# ES_Daisy_Patch_Rev4.net
KiCad netlist of a schematic drawn in EAGLE
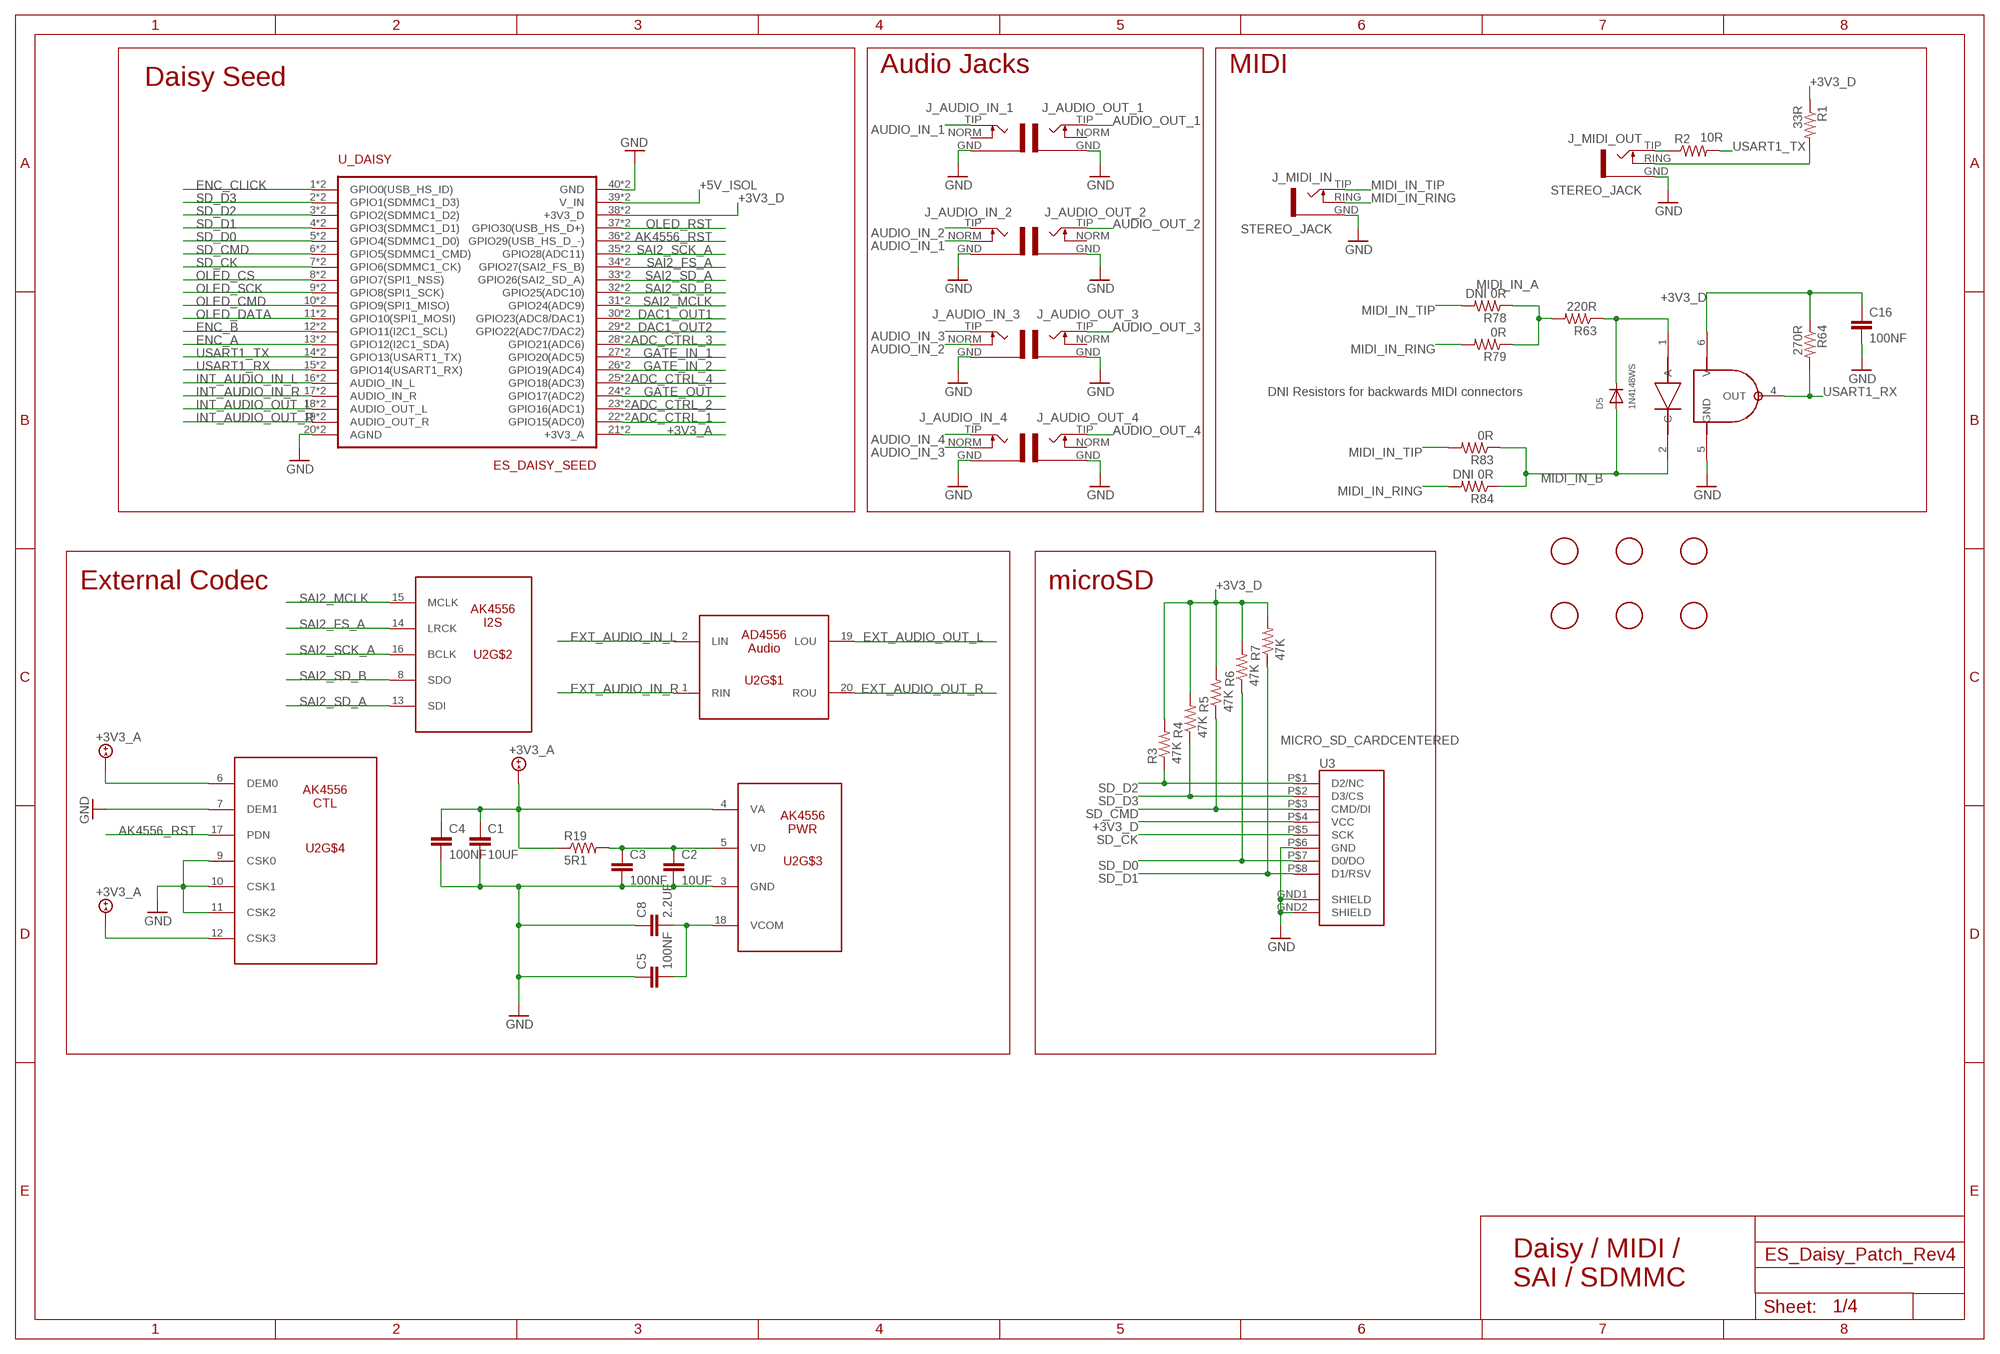
[diagram p0: schematic, sheet 1]
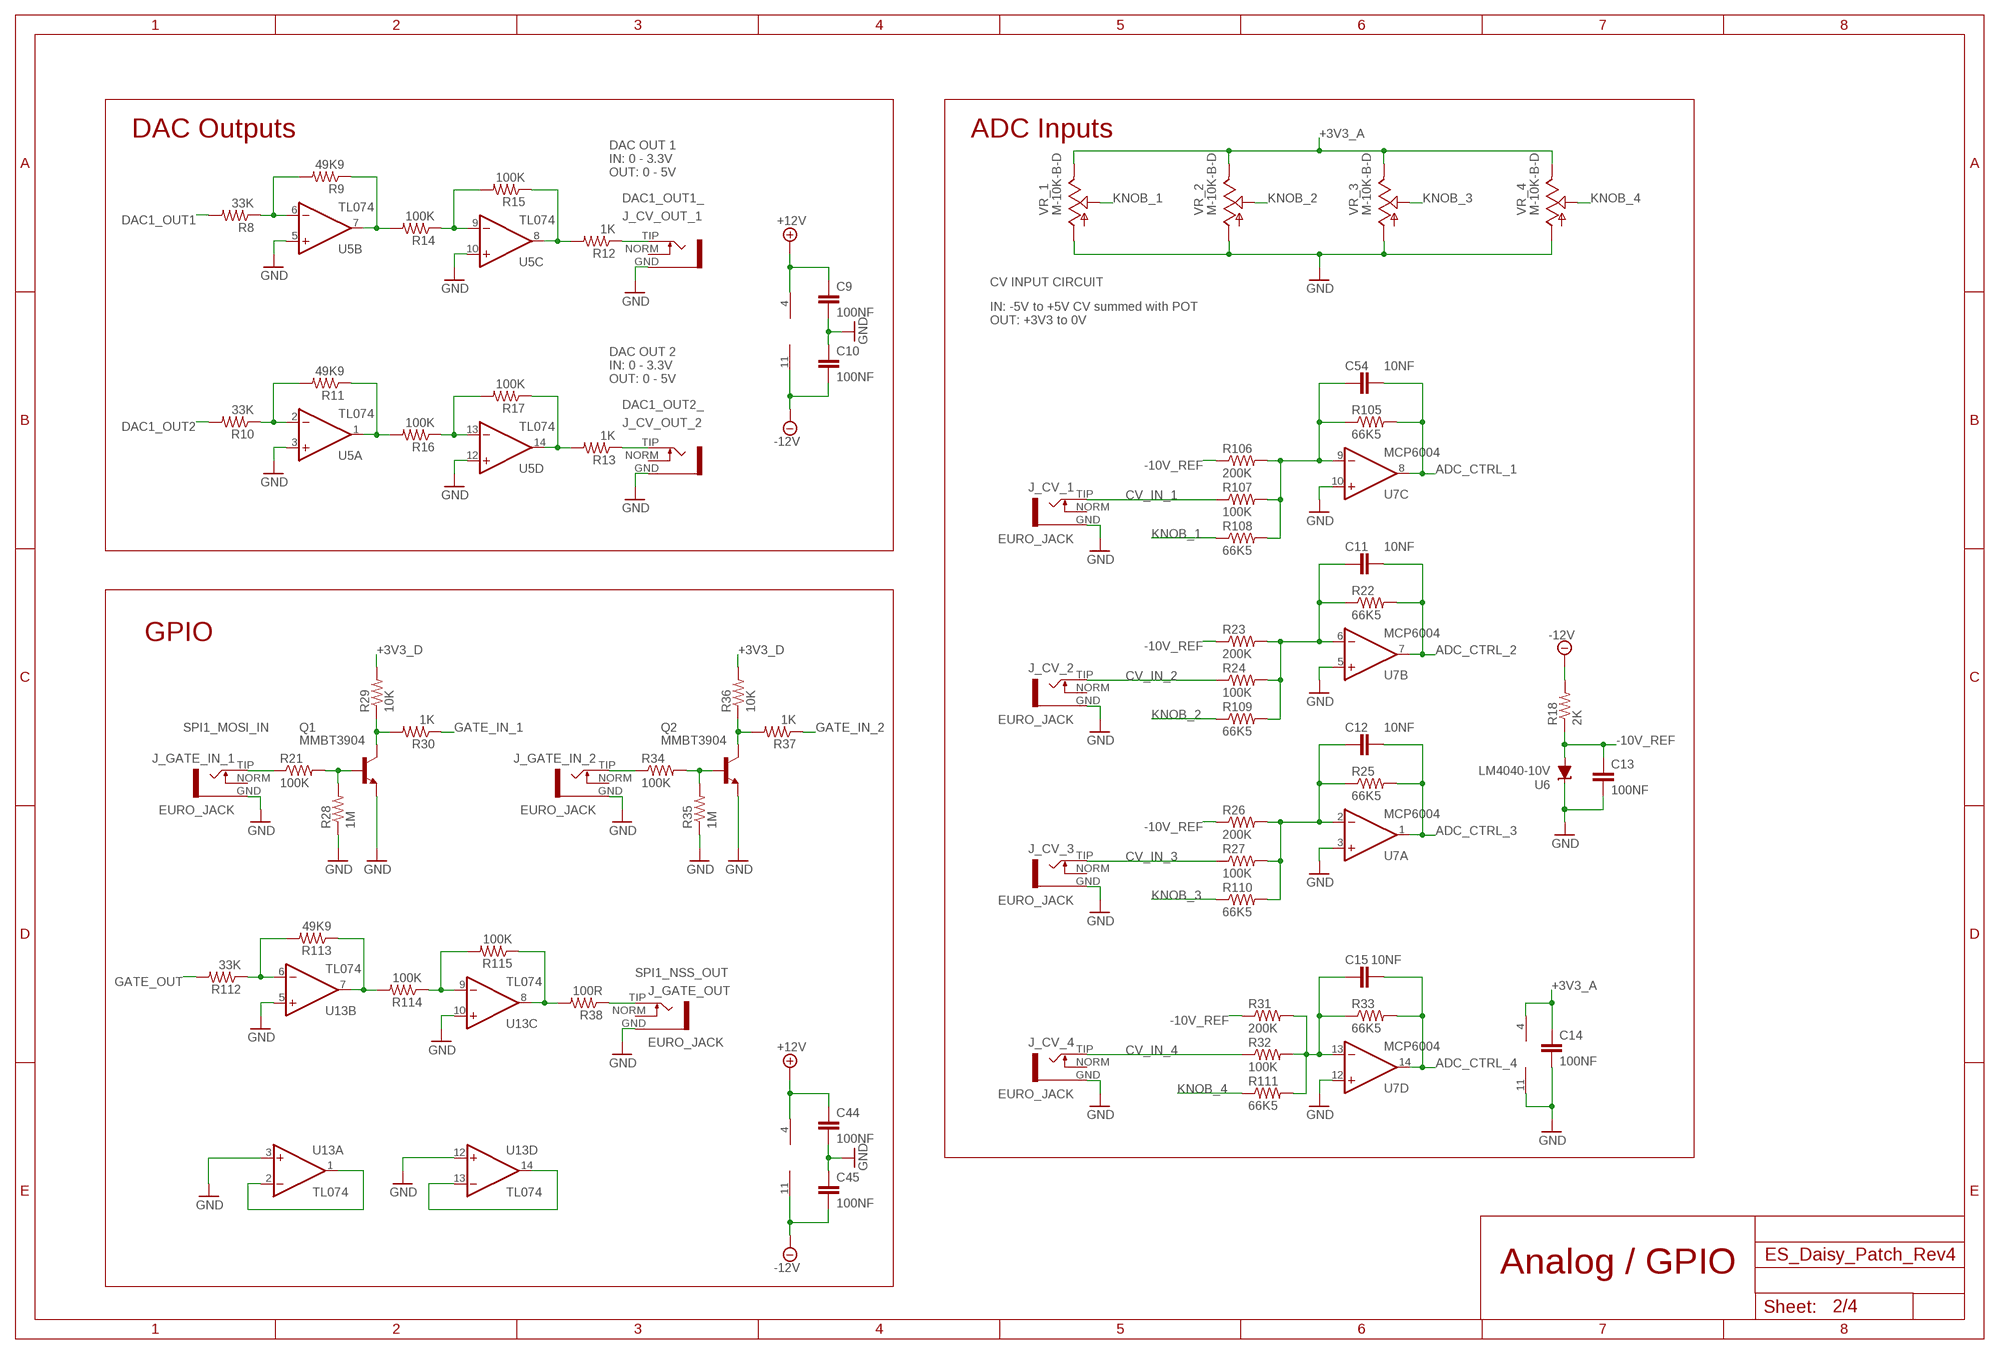
[diagram p1: schematic, sheet 2]
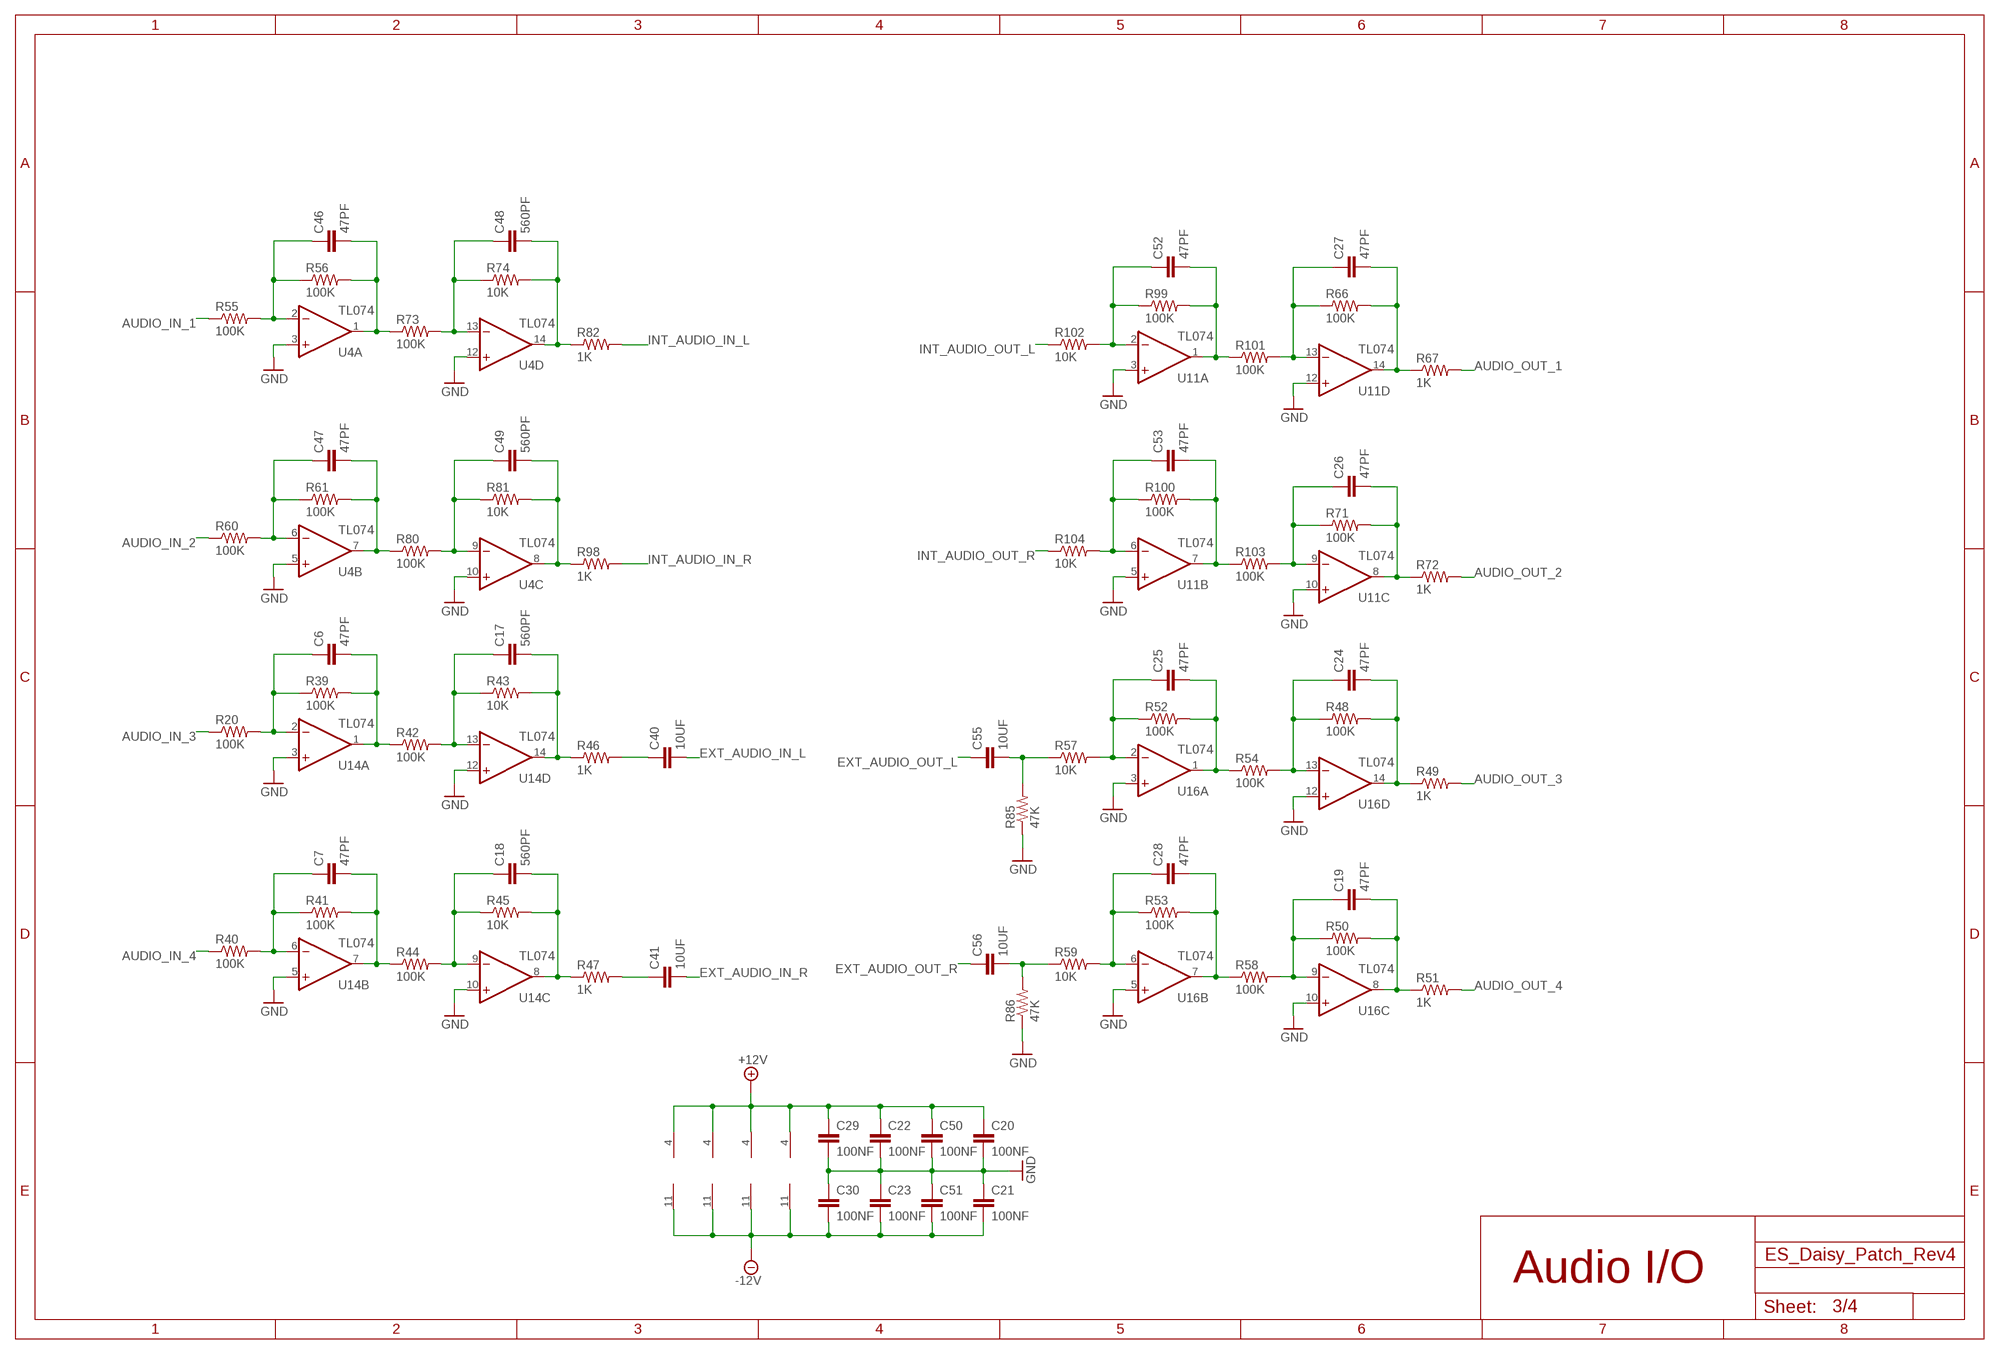
[diagram p2: schematic, sheet 3]
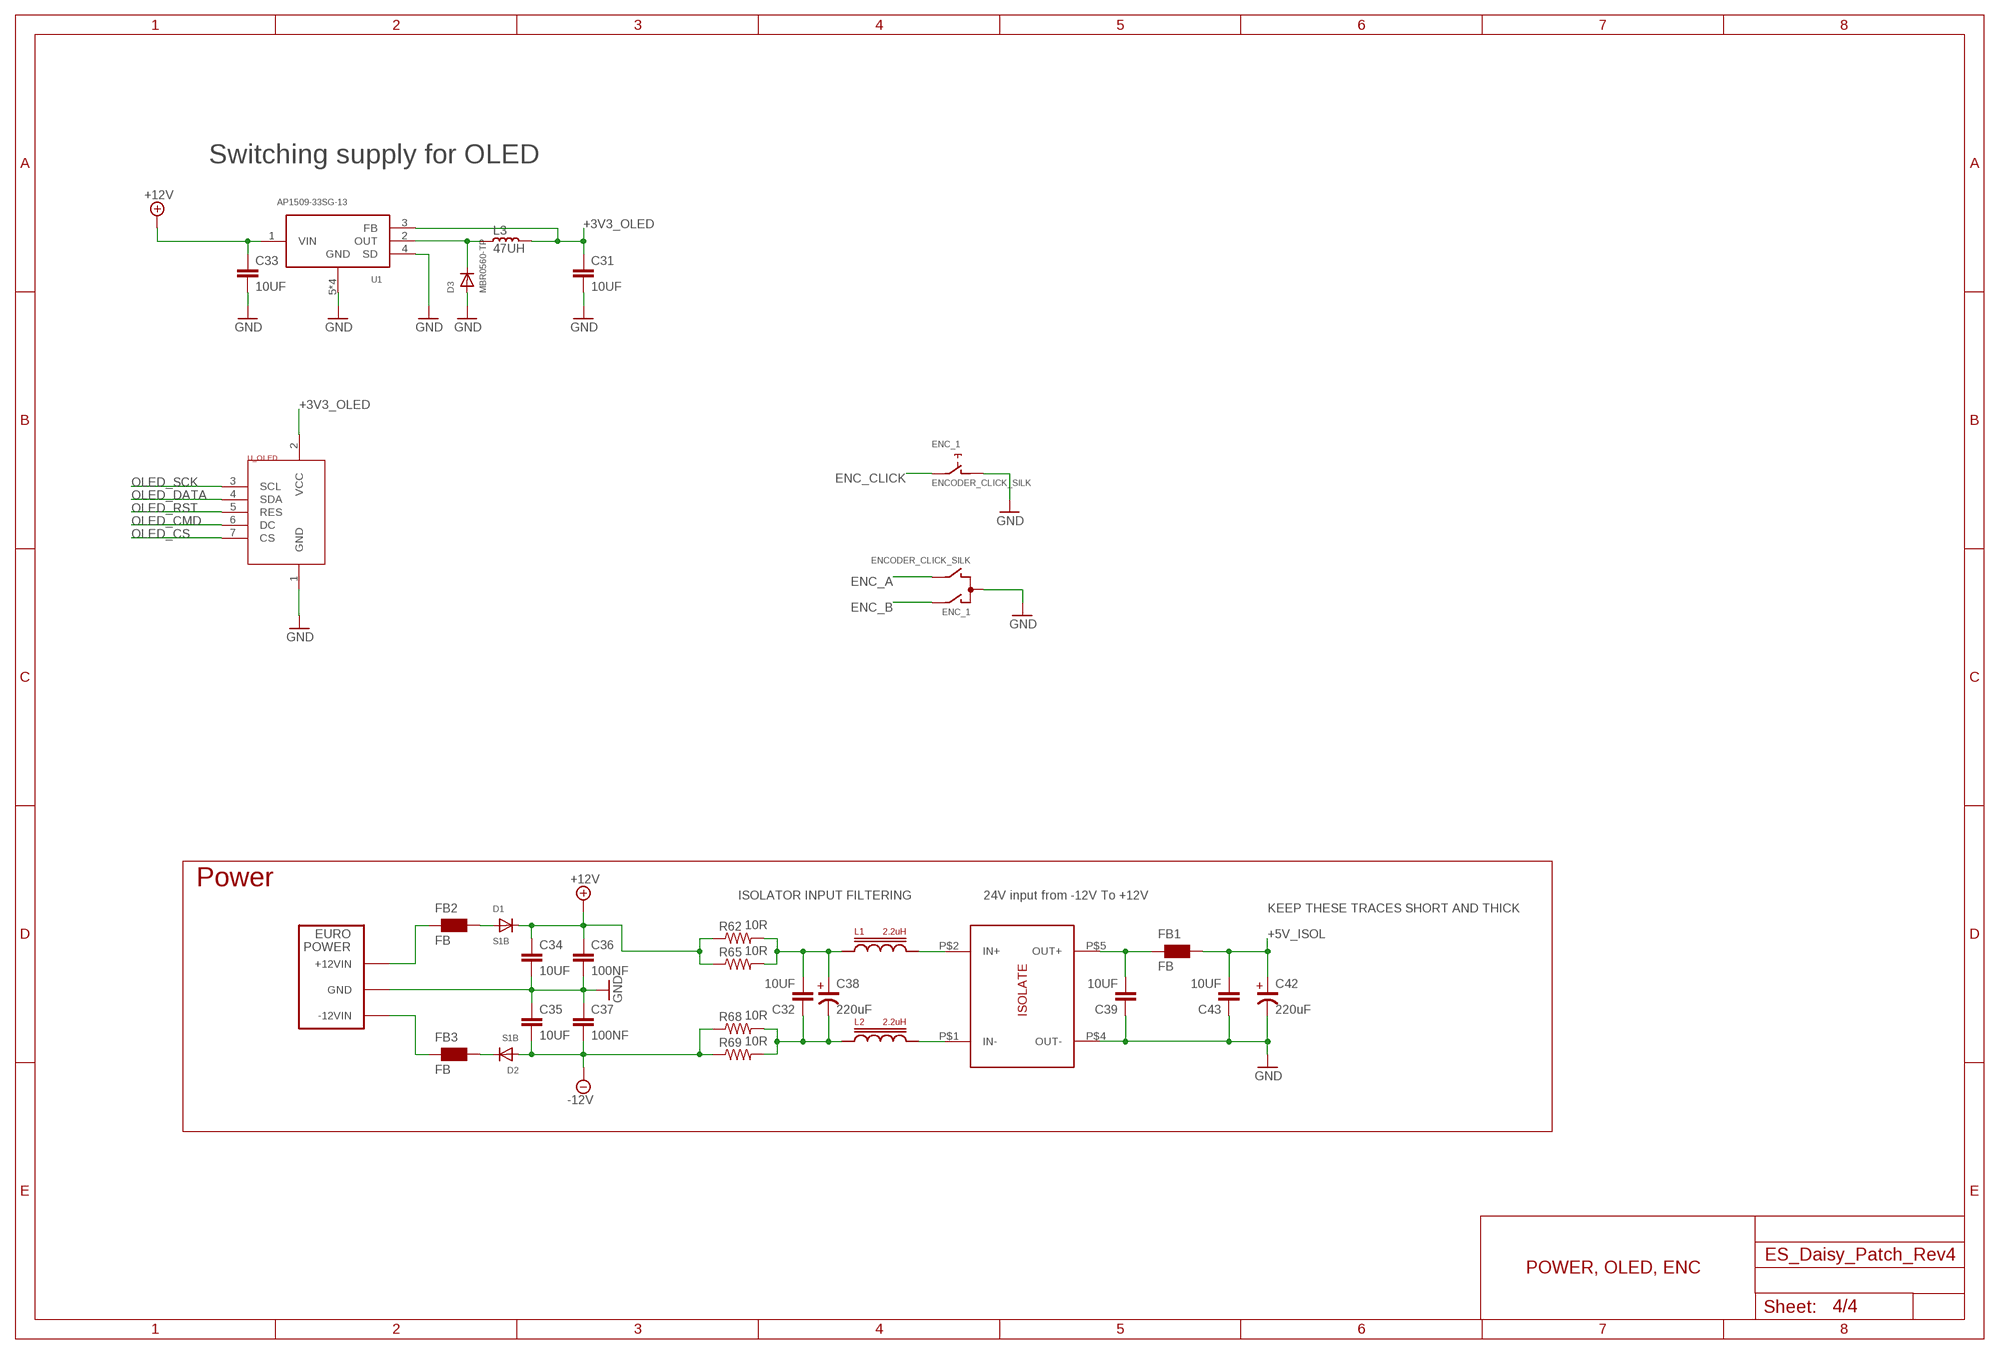
[diagram p3: schematic, sheet 4]

(export (version "E")
  (design (tool "Eeschema 10.0.6"))
  (components
    (comp (ref "C6")
      (value "47PF")
      (footprint "eagle-import:C0603")
      (libsource (lib "eagle-import") (part "Electrosmith-Passives_C-EUC0603"))
    )
    (comp (ref "C7")
      (value "47PF")
      (footprint "eagle-import:C0603")
      (libsource (lib "eagle-import") (part "Electrosmith-Passives_C-EUC0603"))
    )
    (comp (ref "C17")
      (value "560PF")
      (footprint "eagle-import:C0603")
      (libsource (lib "eagle-import") (part "Electrosmith-Passives_C-EUC0603"))
    )
    (comp (ref "C18")
      (value "560PF")
      (footprint "eagle-import:C0603")
      (libsource (lib "eagle-import") (part "Electrosmith-Passives_C-EUC0603"))
    )
    (comp (ref "C19")
      (value "47PF")
      (footprint "eagle-import:C0603")
      (libsource (lib "eagle-import") (part "Electrosmith-Passives_C-EUC0603"))
    )
    (comp (ref "C20")
      (value "100NF")
      (footprint "eagle-import:C0603")
      (libsource (lib "eagle-import") (part "Electrosmith-Passives_C-EUC0603"))
    )
    (comp (ref "C21")
      (value "100NF")
      (footprint "eagle-import:C0603")
      (libsource (lib "eagle-import") (part "Electrosmith-Passives_C-EUC0603"))
    )
    (comp (ref "C22")
      (value "100NF")
      (footprint "eagle-import:C0603")
      (libsource (lib "eagle-import") (part "Electrosmith-Passives_C-EUC0603"))
    )
    (comp (ref "C23")
      (value "100NF")
      (footprint "eagle-import:C0603")
      (libsource (lib "eagle-import") (part "Electrosmith-Passives_C-EUC0603"))
    )
    (comp (ref "C24")
      (value "47PF")
      (footprint "eagle-import:C0603")
      (libsource (lib "eagle-import") (part "Electrosmith-Passives_C-EUC0603"))
    )
    (comp (ref "C25")
      (value "47PF")
      (footprint "eagle-import:C0603")
      (libsource (lib "eagle-import") (part "Electrosmith-Passives_C-EUC0603"))
    )
    (comp (ref "C26")
      (value "47PF")
      (footprint "eagle-import:C0603")
      (libsource (lib "eagle-import") (part "Electrosmith-Passives_C-EUC0603"))
    )
    (comp (ref "C27")
      (value "47PF")
      (footprint "eagle-import:C0603")
      (libsource (lib "eagle-import") (part "Electrosmith-Passives_C-EUC0603"))
    )
    (comp (ref "C28")
      (value "47PF")
      (footprint "eagle-import:C0603")
      (libsource (lib "eagle-import") (part "Electrosmith-Passives_C-EUC0603"))
    )
    (comp (ref "C29")
      (value "100NF")
      (footprint "eagle-import:C0603")
      (libsource (lib "eagle-import") (part "Electrosmith-Passives_C-EUC0603"))
    )
    (comp (ref "C30")
      (value "100NF")
      (footprint "eagle-import:C0603")
      (libsource (lib "eagle-import") (part "Electrosmith-Passives_C-EUC0603"))
    )
    (comp (ref "C40")
      (value "10UF")
      (footprint "eagle-import:C0805")
      (libsource (lib "eagle-import") (part "Electrosmith-Passives_C-EUC0805"))
    )
    (comp (ref "C41")
      (value "10UF")
      (footprint "eagle-import:C0805")
      (libsource (lib "eagle-import") (part "Electrosmith-Passives_C-EUC0805"))
    )
    (comp (ref "C46")
      (value "47PF")
      (footprint "eagle-import:C0603")
      (libsource (lib "eagle-import") (part "Electrosmith-Passives_C-EUC0603"))
    )
    (comp (ref "C47")
      (value "47PF")
      (footprint "eagle-import:C0603")
      (libsource (lib "eagle-import") (part "Electrosmith-Passives_C-EUC0603"))
    )
    (comp (ref "C48")
      (value "560PF")
      (footprint "eagle-import:C0603")
      (libsource (lib "eagle-import") (part "Electrosmith-Passives_C-EUC0603"))
    )
    (comp (ref "C49")
      (value "560PF")
      (footprint "eagle-import:C0603")
      (libsource (lib "eagle-import") (part "Electrosmith-Passives_C-EUC0603"))
    )
    (comp (ref "C50")
      (value "100NF")
      (footprint "eagle-import:C0603")
      (libsource (lib "eagle-import") (part "Electrosmith-Passives_C-EUC0603"))
    )
    (comp (ref "C51")
      (value "100NF")
      (footprint "eagle-import:C0603")
      (libsource (lib "eagle-import") (part "Electrosmith-Passives_C-EUC0603"))
    )
    (comp (ref "C52")
      (value "47PF")
      (footprint "eagle-import:C0603")
      (libsource (lib "eagle-import") (part "Electrosmith-Passives_C-EUC0603"))
    )
    (comp (ref "C53")
      (value "47PF")
      (footprint "eagle-import:C0603")
      (libsource (lib "eagle-import") (part "Electrosmith-Passives_C-EUC0603"))
    )
    (comp (ref "C55")
      (value "10UF")
      (footprint "eagle-import:C0805")
      (libsource (lib "eagle-import") (part "Electrosmith-Passives_C-EUC0805"))
    )
    (comp (ref "C56")
      (value "10UF")
      (footprint "eagle-import:C0805")
      (libsource (lib "eagle-import") (part "Electrosmith-Passives_C-EUC0805"))
    )
    (comp (ref "R20")
      (value "100K")
      (footprint "eagle-import:R0603")
      (libsource (lib "eagle-import") (part "R-US_R0603"))
    )
    (comp (ref "R39")
      (value "100K")
      (footprint "eagle-import:R0603")
      (libsource (lib "eagle-import") (part "R-US_R0603"))
    )
    (comp (ref "R40")
      (value "100K")
      (footprint "eagle-import:R0603")
      (libsource (lib "eagle-import") (part "R-US_R0603"))
    )
    (comp (ref "R41")
      (value "100K")
      (footprint "eagle-import:R0603")
      (libsource (lib "eagle-import") (part "R-US_R0603"))
    )
    (comp (ref "R42")
      (value "100K")
      (footprint "eagle-import:R0603")
      (libsource (lib "eagle-import") (part "R-US_R0603"))
    )
    (comp (ref "R43")
      (value "10K")
      (footprint "eagle-import:R0603")
      (libsource (lib "eagle-import") (part "R-US_R0603"))
    )
    (comp (ref "R44")
      (value "100K")
      (footprint "eagle-import:R0603")
      (libsource (lib "eagle-import") (part "R-US_R0603"))
    )
    (comp (ref "R45")
      (value "10K")
      (footprint "eagle-import:R0603")
      (libsource (lib "eagle-import") (part "R-US_R0603"))
    )
    (comp (ref "R46")
      (value "1K")
      (footprint "eagle-import:R0603")
      (libsource (lib "eagle-import") (part "R-US_R0603"))
    )
    (comp (ref "R47")
      (value "1K")
      (footprint "eagle-import:R0603")
      (libsource (lib "eagle-import") (part "R-US_R0603"))
    )
    (comp (ref "R48")
      (value "100K")
      (footprint "eagle-import:R0603")
      (libsource (lib "eagle-import") (part "R-US_R0603"))
    )
    (comp (ref "R49")
      (value "1K")
      (footprint "eagle-import:R0603")
      (libsource (lib "eagle-import") (part "R-US_R0603"))
    )
    (comp (ref "R50")
      (value "100K")
      (footprint "eagle-import:R0603")
      (libsource (lib "eagle-import") (part "R-US_R0603"))
    )
    (comp (ref "R51")
      (value "1K")
      (footprint "eagle-import:R0603")
      (libsource (lib "eagle-import") (part "R-US_R0603"))
    )
    (comp (ref "R52")
      (value "100K")
      (footprint "eagle-import:R0603")
      (libsource (lib "eagle-import") (part "R-US_R0603"))
    )
    (comp (ref "R53")
      (value "100K")
      (footprint "eagle-import:R0603")
      (libsource (lib "eagle-import") (part "R-US_R0603"))
    )
    (comp (ref "R54")
      (value "100K")
      (footprint "eagle-import:R0603")
      (libsource (lib "eagle-import") (part "R-US_R0603"))
    )
    (comp (ref "R55")
      (value "100K")
      (footprint "eagle-import:R0603")
      (libsource (lib "eagle-import") (part "R-US_R0603"))
    )
    (comp (ref "R56")
      (value "100K")
      (footprint "eagle-import:R0603")
      (libsource (lib "eagle-import") (part "R-US_R0603"))
    )
    (comp (ref "R57")
      (value "10K")
      (footprint "eagle-import:R0603")
      (libsource (lib "eagle-import") (part "R-US_R0603"))
    )
    (comp (ref "R58")
      (value "100K")
      (footprint "eagle-import:R0603")
      (libsource (lib "eagle-import") (part "R-US_R0603"))
    )
    (comp (ref "R59")
      (value "10K")
      (footprint "eagle-import:R0603")
      (libsource (lib "eagle-import") (part "R-US_R0603"))
    )
    (comp (ref "R60")
      (value "100K")
      (footprint "eagle-import:R0603")
      (libsource (lib "eagle-import") (part "R-US_R0603"))
    )
    (comp (ref "R61")
      (value "100K")
      (footprint "eagle-import:R0603")
      (libsource (lib "eagle-import") (part "R-US_R0603"))
    )
    (comp (ref "R66")
      (value "100K")
      (footprint "eagle-import:R0603")
      (libsource (lib "eagle-import") (part "R-US_R0603"))
    )
    (comp (ref "R67")
      (value "1K")
      (footprint "eagle-import:R0603")
      (libsource (lib "eagle-import") (part "R-US_R0603"))
    )
    (comp (ref "R71")
      (value "100K")
      (footprint "eagle-import:R0603")
      (libsource (lib "eagle-import") (part "R-US_R0603"))
    )
    (comp (ref "R72")
      (value "1K")
      (footprint "eagle-import:R0603")
      (libsource (lib "eagle-import") (part "R-US_R0603"))
    )
    (comp (ref "R73")
      (value "100K")
      (footprint "eagle-import:R0603")
      (libsource (lib "eagle-import") (part "R-US_R0603"))
    )
    (comp (ref "R74")
      (value "10K")
      (footprint "eagle-import:R0603")
      (libsource (lib "eagle-import") (part "R-US_R0603"))
    )
    (comp (ref "R80")
      (value "100K")
      (footprint "eagle-import:R0603")
      (libsource (lib "eagle-import") (part "R-US_R0603"))
    )
    (comp (ref "R81")
      (value "10K")
      (footprint "eagle-import:R0603")
      (libsource (lib "eagle-import") (part "R-US_R0603"))
    )
    (comp (ref "R82")
      (value "1K")
      (footprint "eagle-import:R0603")
      (libsource (lib "eagle-import") (part "R-US_R0603"))
    )
    (comp (ref "R85")
      (value "47K")
      (footprint "eagle-import:R0603")
      (libsource (lib "eagle-import") (part "R-US_R0603"))
    )
    (comp (ref "R86")
      (value "47K")
      (footprint "eagle-import:R0603")
      (libsource (lib "eagle-import") (part "R-US_R0603"))
    )
    (comp (ref "R98")
      (value "1K")
      (footprint "eagle-import:R0603")
      (libsource (lib "eagle-import") (part "R-US_R0603"))
    )
    (comp (ref "R99")
      (value "100K")
      (footprint "eagle-import:R0603")
      (libsource (lib "eagle-import") (part "R-US_R0603"))
    )
    (comp (ref "R100")
      (value "100K")
      (footprint "eagle-import:R0603")
      (libsource (lib "eagle-import") (part "R-US_R0603"))
    )
    (comp (ref "R101")
      (value "100K")
      (footprint "eagle-import:R0603")
      (libsource (lib "eagle-import") (part "R-US_R0603"))
    )
    (comp (ref "R102")
      (value "10K")
      (footprint "eagle-import:R0603")
      (libsource (lib "eagle-import") (part "R-US_R0603"))
    )
    (comp (ref "R103")
      (value "100K")
      (footprint "eagle-import:R0603")
      (libsource (lib "eagle-import") (part "R-US_R0603"))
    )
    (comp (ref "R104")
      (value "10K")
      (footprint "eagle-import:R0603")
      (libsource (lib "eagle-import") (part "R-US_R0603"))
    )
    (comp (ref "U4")
      (value "TL074")
      (footprint "eagle-import:TSSOP-14")
      (fields (field (name "MPN") "TL074CPWR"))
      (libsource (lib "eagle-import") (part "TL074_TSSOP-14"))
    )
    (comp (ref "U11")
      (value "TL074")
      (footprint "eagle-import:TSSOP-14")
      (fields (field (name "MPN") "TL074CPWR"))
      (libsource (lib "eagle-import") (part "TL074_TSSOP-14"))
    )
    (comp (ref "U14")
      (value "TL074")
      (footprint "eagle-import:TSSOP-14")
      (fields (field (name "MPN") "TL074CPWR"))
      (libsource (lib "eagle-import") (part "TL074_TSSOP-14"))
    )
    (comp (ref "U16")
      (value "TL074")
      (footprint "eagle-import:TSSOP-14")
      (fields (field (name "MPN") "TL074CPWR"))
      (libsource (lib "eagle-import") (part "TL074_TSSOP-14"))
    )
    (comp (ref "C1")
      (value "10UF")
      (footprint "eagle-import:C0805")
      (libsource (lib "eagle-import") (part "Electrosmith-Passives_C-EUC0805"))
    )
    (comp (ref "C2")
      (value "10UF")
      (footprint "eagle-import:C0805")
      (libsource (lib "eagle-import") (part "Electrosmith-Passives_C-EUC0805"))
    )
    (comp (ref "C3")
      (value "100NF")
      (footprint "eagle-import:C0603")
      (libsource (lib "eagle-import") (part "Electrosmith-Passives_C-EUC0603"))
    )
    (comp (ref "C4")
      (value "100NF")
      (footprint "eagle-import:C0603")
      (libsource (lib "eagle-import") (part "Electrosmith-Passives_C-EUC0603"))
    )
    (comp (ref "C5")
      (value "100NF")
      (footprint "eagle-import:C0603")
      (libsource (lib "eagle-import") (part "Electrosmith-Passives_C-EUC0603"))
    )
    (comp (ref "C8")
      (value "2.2UF")
      (footprint "eagle-import:C0603")
      (libsource (lib "eagle-import") (part "Electrosmith-Passives_C-EUC0603"))
    )
    (comp (ref "C16")
      (value "100NF")
      (footprint "eagle-import:C0603")
      (libsource (lib "eagle-import") (part "Electrosmith-Passives_C-EUC0603"))
    )
    (comp (ref "D5")
      (value "1N4148WS")
      (footprint "eagle-import:SOD-323F")
      (libsource (lib "eagle-import") (part "DIODE_SOD-323F"))
    )
    (comp (ref "FD1")
      (value "FIDUCIAL")
      (footprint "eagle-import:FIDUCIAL_1MM")
      (libsource (lib "eagle-import") (part "FIDUCIAL"))
    )
    (comp (ref "FD2")
      (value "FIDUCIAL")
      (footprint "eagle-import:FIDUCIAL_1MM")
      (libsource (lib "eagle-import") (part "FIDUCIAL"))
    )
    (comp (ref "FD3")
      (value "FIDUCIAL")
      (footprint "eagle-import:FIDUCIAL_1MM")
      (libsource (lib "eagle-import") (part "FIDUCIAL"))
    )
    (comp (ref "FD4")
      (value "FIDUCIAL")
      (footprint "eagle-import:FIDUCIAL_1MM")
      (libsource (lib "eagle-import") (part "FIDUCIAL"))
    )
    (comp (ref "FD5")
      (value "FIDUCIAL")
      (footprint "eagle-import:FIDUCIAL_1MM")
      (libsource (lib "eagle-import") (part "FIDUCIAL"))
    )
    (comp (ref "FD6")
      (value "FIDUCIAL")
      (footprint "eagle-import:FIDUCIAL_1MM")
      (libsource (lib "eagle-import") (part "FIDUCIAL"))
    )
    (comp (ref "J_AUDIO_IN_1")
      (value "EURO_JACK")
      (footprint "eagle-import:S_JACK")
      (libsource (lib "eagle-import") (part "EURO_JACK"))
    )
    (comp (ref "J_AUDIO_IN_2")
      (value "EURO_JACK")
      (footprint "eagle-import:S_JACK")
      (libsource (lib "eagle-import") (part "EURO_JACK"))
    )
    (comp (ref "J_AUDIO_IN_3")
      (value "EURO_JACK")
      (footprint "eagle-import:S_JACK")
      (libsource (lib "eagle-import") (part "EURO_JACK"))
    )
    (comp (ref "J_AUDIO_IN_4")
      (value "EURO_JACK")
      (footprint "eagle-import:S_JACK")
      (libsource (lib "eagle-import") (part "EURO_JACK"))
    )
    (comp (ref "J_AUDIO_OUT_1")
      (value "EURO_JACK")
      (footprint "eagle-import:S_JACK")
      (libsource (lib "eagle-import") (part "EURO_JACK"))
    )
    (comp (ref "J_AUDIO_OUT_2")
      (value "EURO_JACK")
      (footprint "eagle-import:S_JACK")
      (libsource (lib "eagle-import") (part "EURO_JACK"))
    )
    (comp (ref "J_AUDIO_OUT_3")
      (value "EURO_JACK")
      (footprint "eagle-import:S_JACK")
      (libsource (lib "eagle-import") (part "EURO_JACK"))
    )
    (comp (ref "J_AUDIO_OUT_4")
      (value "EURO_JACK")
      (footprint "eagle-import:S_JACK")
      (libsource (lib "eagle-import") (part "EURO_JACK"))
    )
    (comp (ref "J_MIDI_IN")
      (value "STEREO_JACK")
      (footprint "eagle-import:STEREO_JACK_3.5MM")
      (libsource (lib "eagle-import") (part "STEREO_JACK"))
    )
    (comp (ref "J_MIDI_OUT")
      (value "STEREO_JACK")
      (footprint "eagle-import:STEREO_JACK_3.5MM")
      (libsource (lib "eagle-import") (part "STEREO_JACK"))
    )
    (comp (ref "R1")
      (value "33R")
      (footprint "eagle-import:R0603")
      (libsource (lib "eagle-import") (part "R-US_R0603"))
    )
    (comp (ref "R2")
      (value "10R")
      (footprint "eagle-import:R0603")
      (libsource (lib "eagle-import") (part "R-US_R0603"))
    )
    (comp (ref "R3")
      (value "47K")
      (footprint "eagle-import:R0603")
      (libsource (lib "eagle-import") (part "R-US_R0603"))
    )
    (comp (ref "R4")
      (value "47K")
      (footprint "eagle-import:R0603")
      (libsource (lib "eagle-import") (part "R-US_R0603"))
    )
    (comp (ref "R5")
      (value "47K")
      (footprint "eagle-import:R0603")
      (libsource (lib "eagle-import") (part "R-US_R0603"))
    )
    (comp (ref "R6")
      (value "47K")
      (footprint "eagle-import:R0603")
      (libsource (lib "eagle-import") (part "R-US_R0603"))
    )
    (comp (ref "R7")
      (value "47K")
      (footprint "eagle-import:R0603")
      (libsource (lib "eagle-import") (part "R-US_R0603"))
    )
    (comp (ref "R19")
      (value "5R1")
      (footprint "eagle-import:R0603")
      (libsource (lib "eagle-import") (part "R-US_R0603"))
    )
    (comp (ref "R63")
      (value "220R")
      (footprint "eagle-import:R0603")
      (libsource (lib "eagle-import") (part "R-US_R0603"))
    )
    (comp (ref "R64")
      (value "270R")
      (footprint "eagle-import:R0603")
      (libsource (lib "eagle-import") (part "R-US_R0603"))
    )
    (comp (ref "R78")
      (value "DNI 0R")
      (footprint "eagle-import:R0603")
      (libsource (lib "eagle-import") (part "R-US_R0603"))
    )
    (comp (ref "R79")
      (value "0R")
      (footprint "eagle-import:R0603")
      (libsource (lib "eagle-import") (part "R-US_R0603"))
    )
    (comp (ref "R83")
      (value "0R")
      (footprint "eagle-import:R0603")
      (libsource (lib "eagle-import") (part "R-US_R0603"))
    )
    (comp (ref "R84")
      (value "DNI 0R")
      (footprint "eagle-import:R0603")
      (libsource (lib "eagle-import") (part "R-US_R0603"))
    )
    (comp (ref "U2")
      (value "AK4556")
      (footprint "eagle-import:TSSOP20")
      (libsource (lib "eagle-import") (part "AK4556"))
    )
    (comp (ref "U3")
      (value "MICRO_SD_CARDCENTERED")
      (footprint "eagle-import:VERT_MICROSD_CENTERED")
      (libsource (lib "eagle-import") (part "MICRO_SD_CARDCENTERED"))
    )
    (comp (ref "U15")
      (value "OPTOISOLATOR_H11L1M")
      (footprint "eagle-import:DIL06_GULLWING")
      (fields (field (name "MPN") "H11L1SR2M"))
      (libsource (lib "eagle-import") (part "OPTOISOLATOR_H11L1M"))
    )
    (comp (ref "U_DAISY")
      (value "ES_DAISY_SEED")
      (footprint "eagle-import:ES_DAISY_SEED_DOUBLE")
      (libsource (lib "eagle-import") (part "ES_DAISY_SEED_REV4_DOUBLE"))
    )
    (comp (ref "C9")
      (value "100NF")
      (footprint "eagle-import:C0603")
      (libsource (lib "eagle-import") (part "Electrosmith-Passives_C-EUC0603"))
    )
    (comp (ref "C10")
      (value "100NF")
      (footprint "eagle-import:C0603")
      (libsource (lib "eagle-import") (part "Electrosmith-Passives_C-EUC0603"))
    )
    (comp (ref "C11")
      (value "10NF")
      (footprint "eagle-import:C0603")
      (libsource (lib "eagle-import") (part "Electrosmith-Passives_C-EUC0603"))
    )
    (comp (ref "C12")
      (value "10NF")
      (footprint "eagle-import:C0603")
      (libsource (lib "eagle-import") (part "Electrosmith-Passives_C-EUC0603"))
    )
    (comp (ref "C13")
      (value "100NF")
      (footprint "eagle-import:C0603")
      (libsource (lib "eagle-import") (part "Electrosmith-Passives_C-EUC0603"))
    )
    (comp (ref "C14")
      (value "100NF")
      (footprint "eagle-import:C0603")
      (libsource (lib "eagle-import") (part "Electrosmith-Passives_C-EUC0603"))
    )
    (comp (ref "C15")
      (value "10NF")
      (footprint "eagle-import:C0603")
      (libsource (lib "eagle-import") (part "Electrosmith-Passives_C-EUC0603"))
    )
    (comp (ref "C44")
      (value "100NF")
      (footprint "eagle-import:C0603")
      (libsource (lib "eagle-import") (part "Electrosmith-Passives_C-EUC0603"))
    )
    (comp (ref "C45")
      (value "100NF")
      (footprint "eagle-import:C0603")
      (libsource (lib "eagle-import") (part "Electrosmith-Passives_C-EUC0603"))
    )
    (comp (ref "C54")
      (value "10NF")
      (footprint "eagle-import:C0603")
      (libsource (lib "eagle-import") (part "Electrosmith-Passives_C-EUC0603"))
    )
    (comp (ref "J_CV_1")
      (value "EURO_JACK")
      (footprint "eagle-import:S_JACK")
      (libsource (lib "eagle-import") (part "EURO_JACK"))
    )
    (comp (ref "J_CV_2")
      (value "EURO_JACK")
      (footprint "eagle-import:S_JACK")
      (libsource (lib "eagle-import") (part "EURO_JACK"))
    )
    (comp (ref "J_CV_3")
      (value "EURO_JACK")
      (footprint "eagle-import:S_JACK")
      (libsource (lib "eagle-import") (part "EURO_JACK"))
    )
    (comp (ref "J_CV_4")
      (value "EURO_JACK")
      (footprint "eagle-import:S_JACK")
      (libsource (lib "eagle-import") (part "EURO_JACK"))
    )
    (comp (ref "J_CV_OUT_1")
      (value "EURO_JACK")
      (footprint "eagle-import:S_JACK")
      (libsource (lib "eagle-import") (part "EURO_JACK"))
    )
    (comp (ref "J_CV_OUT_2")
      (value "EURO_JACK")
      (footprint "eagle-import:S_JACK")
      (libsource (lib "eagle-import") (part "EURO_JACK"))
    )
    (comp (ref "J_GATE_IN_1")
      (value "EURO_JACK")
      (footprint "eagle-import:S_JACK")
      (libsource (lib "eagle-import") (part "EURO_JACK"))
    )
    (comp (ref "J_GATE_IN_2")
      (value "EURO_JACK")
      (footprint "eagle-import:S_JACK")
      (libsource (lib "eagle-import") (part "EURO_JACK"))
    )
    (comp (ref "J_GATE_OUT")
      (value "EURO_JACK")
      (footprint "eagle-import:S_JACK")
      (libsource (lib "eagle-import") (part "EURO_JACK"))
    )
    (comp (ref "Q1")
      (value "MMBT3904")
      (footprint "eagle-import:SOT23-BEC")
      (libsource (lib "eagle-import") (part "NPNSOT23-BEC"))
    )
    (comp (ref "Q2")
      (value "MMBT3904")
      (footprint "eagle-import:SOT23-BEC")
      (libsource (lib "eagle-import") (part "NPNSOT23-BEC"))
    )
    (comp (ref "R8")
      (value "33K")
      (footprint "eagle-import:R0603")
      (libsource (lib "eagle-import") (part "R-US_R0603"))
    )
    (comp (ref "R9")
      (value "49K9")
      (footprint "eagle-import:R0603")
      (libsource (lib "eagle-import") (part "R-US_R0603"))
    )
    (comp (ref "R10")
      (value "33K")
      (footprint "eagle-import:R0603")
      (libsource (lib "eagle-import") (part "R-US_R0603"))
    )
    (comp (ref "R11")
      (value "49K9")
      (footprint "eagle-import:R0603")
      (libsource (lib "eagle-import") (part "R-US_R0603"))
    )
    (comp (ref "R12")
      (value "1K")
      (footprint "eagle-import:R0603")
      (libsource (lib "eagle-import") (part "R-US_R0603"))
    )
    (comp (ref "R13")
      (value "1K")
      (footprint "eagle-import:R0603")
      (libsource (lib "eagle-import") (part "R-US_R0603"))
    )
    (comp (ref "R14")
      (value "100K")
      (footprint "eagle-import:R0603")
      (libsource (lib "eagle-import") (part "R-US_R0603"))
    )
    (comp (ref "R15")
      (value "100K")
      (footprint "eagle-import:R0603")
      (libsource (lib "eagle-import") (part "R-US_R0603"))
    )
    (comp (ref "R16")
      (value "100K")
      (footprint "eagle-import:R0603")
      (libsource (lib "eagle-import") (part "R-US_R0603"))
    )
    (comp (ref "R17")
      (value "100K")
      (footprint "eagle-import:R0603")
      (libsource (lib "eagle-import") (part "R-US_R0603"))
    )
    (comp (ref "R18")
      (value "2K")
      (footprint "eagle-import:R0603")
      (libsource (lib "eagle-import") (part "R-US_R0603"))
    )
    (comp (ref "R21")
      (value "100K")
      (footprint "eagle-import:R0603")
      (libsource (lib "eagle-import") (part "R-US_R0603"))
    )
    (comp (ref "R22")
      (value "66K5")
      (footprint "eagle-import:R0603")
      (libsource (lib "eagle-import") (part "R-US_R0603"))
    )
    (comp (ref "R23")
      (value "200K")
      (footprint "eagle-import:R0603")
      (libsource (lib "eagle-import") (part "R-US_R0603"))
    )
    (comp (ref "R24")
      (value "100K")
      (footprint "eagle-import:R0603")
      (libsource (lib "eagle-import") (part "R-US_R0603"))
    )
    (comp (ref "R25")
      (value "66K5")
      (footprint "eagle-import:R0603")
      (libsource (lib "eagle-import") (part "R-US_R0603"))
    )
    (comp (ref "R26")
      (value "200K")
      (footprint "eagle-import:R0603")
      (libsource (lib "eagle-import") (part "R-US_R0603"))
    )
    (comp (ref "R27")
      (value "100K")
      (footprint "eagle-import:R0603")
      (libsource (lib "eagle-import") (part "R-US_R0603"))
    )
    (comp (ref "R28")
      (value "1M")
      (footprint "eagle-import:R0603")
      (libsource (lib "eagle-import") (part "R-US_R0603"))
    )
    (comp (ref "R29")
      (value "10K")
      (footprint "eagle-import:R0603")
      (libsource (lib "eagle-import") (part "R-US_R0603"))
    )
    (comp (ref "R30")
      (value "1K")
      (footprint "eagle-import:R0603")
      (libsource (lib "eagle-import") (part "R-US_R0603"))
    )
    (comp (ref "R31")
      (value "200K")
      (footprint "eagle-import:R0603")
      (libsource (lib "eagle-import") (part "R-US_R0603"))
    )
    (comp (ref "R32")
      (value "100K")
      (footprint "eagle-import:R0603")
      (libsource (lib "eagle-import") (part "R-US_R0603"))
    )
    (comp (ref "R33")
      (value "66K5")
      (footprint "eagle-import:R0603")
      (libsource (lib "eagle-import") (part "R-US_R0603"))
    )
    (comp (ref "R34")
      (value "100K")
      (footprint "eagle-import:R0603")
      (libsource (lib "eagle-import") (part "R-US_R0603"))
    )
    (comp (ref "R35")
      (value "1M")
      (footprint "eagle-import:R0603")
      (libsource (lib "eagle-import") (part "R-US_R0603"))
    )
    (comp (ref "R36")
      (value "10K")
      (footprint "eagle-import:R0603")
      (libsource (lib "eagle-import") (part "R-US_R0603"))
    )
    (comp (ref "R37")
      (value "1K")
      (footprint "eagle-import:R0603")
      (libsource (lib "eagle-import") (part "R-US_R0603"))
    )
    (comp (ref "R38")
      (value "100R")
      (footprint "eagle-import:R0603")
      (libsource (lib "eagle-import") (part "R-US_R0603"))
    )
    (comp (ref "R105")
      (value "66K5")
      (footprint "eagle-import:R0603")
      (libsource (lib "eagle-import") (part "R-US_R0603"))
    )
    (comp (ref "R106")
      (value "200K")
      (footprint "eagle-import:R0603")
      (libsource (lib "eagle-import") (part "R-US_R0603"))
    )
    (comp (ref "R107")
      (value "100K")
      (footprint "eagle-import:R0603")
      (libsource (lib "eagle-import") (part "R-US_R0603"))
    )
    (comp (ref "R108")
      (value "66K5")
      (footprint "eagle-import:R0603")
      (libsource (lib "eagle-import") (part "R-US_R0603"))
    )
    (comp (ref "R109")
      (value "66K5")
      (footprint "eagle-import:R0603")
      (libsource (lib "eagle-import") (part "R-US_R0603"))
    )
    (comp (ref "R110")
      (value "66K5")
      (footprint "eagle-import:R0603")
      (libsource (lib "eagle-import") (part "R-US_R0603"))
    )
    (comp (ref "R111")
      (value "66K5")
      (footprint "eagle-import:R0603")
      (libsource (lib "eagle-import") (part "R-US_R0603"))
    )
    (comp (ref "R112")
      (value "33K")
      (footprint "eagle-import:R0603")
      (libsource (lib "eagle-import") (part "R-US_R0603"))
    )
    (comp (ref "R113")
      (value "49K9")
      (footprint "eagle-import:R0603")
      (libsource (lib "eagle-import") (part "R-US_R0603"))
    )
    (comp (ref "R114")
      (value "100K")
      (footprint "eagle-import:R0603")
      (libsource (lib "eagle-import") (part "R-US_R0603"))
    )
    (comp (ref "R115")
      (value "100K")
      (footprint "eagle-import:R0603")
      (libsource (lib "eagle-import") (part "R-US_R0603"))
    )
    (comp (ref "U5")
      (value "TL074")
      (footprint "eagle-import:TSSOP-14")
      (fields (field (name "MPN") "TL074CPWR"))
      (libsource (lib "eagle-import") (part "TL074_TSSOP-14"))
    )
    (comp (ref "U6")
      (value "LM4040-10V")
      (footprint "eagle-import:DBZ_R-PDSO-G3")
      (fields (field (name "MPN") "LM4041A12IDBZR"))
      (libsource (lib "eagle-import") (part "LM4040-10VDBZA12"))
    )
    (comp (ref "U7")
      (value "MCP6004")
      (footprint "eagle-import:TSSOP-14")
      (fields (field (name "MPN") "MCP6004T-E/ST"))
      (libsource (lib "eagle-import") (part "MCP6004_TSSOP-14"))
    )
    (comp (ref "U13")
      (value "TL074")
      (footprint "eagle-import:TSSOP-14")
      (fields (field (name "MPN") "TL074CPWR"))
      (libsource (lib "eagle-import") (part "TL074_TSSOP-14"))
    )
    (comp (ref "VR_1")
      (value "M-10K-B-D")
      (footprint "eagle-import:9MM_SNAP-IN_POT_SILK")
      (libsource (lib "eagle-import") (part "POT_9MM_SNAP-IN__"))
    )
    (comp (ref "VR_2")
      (value "M-10K-B-D")
      (footprint "eagle-import:9MM_SNAP-IN_POT_SILK")
      (libsource (lib "eagle-import") (part "POT_9MM_SNAP-IN__"))
    )
    (comp (ref "VR_3")
      (value "M-10K-B-D")
      (footprint "eagle-import:9MM_SNAP-IN_POT_SILK")
      (libsource (lib "eagle-import") (part "POT_9MM_SNAP-IN__"))
    )
    (comp (ref "VR_4")
      (value "M-10K-B-D")
      (footprint "eagle-import:9MM_SNAP-IN_POT_SILK")
      (libsource (lib "eagle-import") (part "POT_9MM_SNAP-IN__"))
    )
    (comp (ref "C31")
      (value "10UF")
      (footprint "eagle-import:C0805")
      (libsource (lib "eagle-import") (part "C-EUC0805"))
    )
    (comp (ref "C32")
      (value "10UF")
      (footprint "eagle-import:C0805")
      (libsource (lib "eagle-import") (part "Electrosmith-Passives_C-EUC0805"))
    )
    (comp (ref "C33")
      (value "10UF")
      (footprint "eagle-import:C0805")
      (libsource (lib "eagle-import") (part "C-EUC0805"))
    )
    (comp (ref "C34")
      (value "10UF")
      (footprint "eagle-import:C0805")
      (libsource (lib "eagle-import") (part "Electrosmith-Passives_C-EUC0805"))
    )
    (comp (ref "C35")
      (value "10UF")
      (footprint "eagle-import:C0805")
      (libsource (lib "eagle-import") (part "Electrosmith-Passives_C-EUC0805"))
    )
    (comp (ref "C36")
      (value "100NF")
      (footprint "eagle-import:C0603")
      (libsource (lib "eagle-import") (part "Electrosmith-Passives_C-EUC0603"))
    )
    (comp (ref "C37")
      (value "100NF")
      (footprint "eagle-import:C0603")
      (libsource (lib "eagle-import") (part "Electrosmith-Passives_C-EUC0603"))
    )
    (comp (ref "C38")
      (value "220uF")
      (footprint "eagle-import:PANASONIC_D")
      (libsource (lib "eagle-import") (part "C-EU-POL_D"))
    )
    (comp (ref "C39")
      (value "10UF")
      (footprint "eagle-import:C0805")
      (libsource (lib "eagle-import") (part "Electrosmith-Passives_C-EUC0805"))
    )
    (comp (ref "C42")
      (value "220uF")
      (footprint "eagle-import:PANASONIC_D")
      (libsource (lib "eagle-import") (part "C-EU-POL_D"))
    )
    (comp (ref "C43")
      (value "10UF")
      (footprint "eagle-import:C0805")
      (libsource (lib "eagle-import") (part "Electrosmith-Passives_C-EUC0805"))
    )
    (comp (ref "D1")
      (value "S1B")
      (footprint "eagle-import:SMADIODE")
      (libsource (lib "eagle-import") (part "S1B"))
    )
    (comp (ref "D2")
      (value "S1B")
      (footprint "eagle-import:SMADIODE")
      (libsource (lib "eagle-import") (part "S1B"))
    )
    (comp (ref "D3")
      (value "MBR0560-TP")
      (footprint "eagle-import:SOD-123")
      (libsource (lib "eagle-import") (part "DIODESOD-123"))
    )
    (comp (ref "ENC_1")
      (value "ENCODER_CLICK_SILK")
      (footprint "eagle-import:PEC11_SILK")
      (libsource (lib "eagle-import") (part "ENCODERSILK_CLICK_"))
    )
    (comp (ref "EP1")
      (value "EURORACK_POWERSMT")
      (footprint "eagle-import:EURORACK_POWER_SMT")
      (fields (field (name "MANF") "FCI") (field (name "MPN") "54202-G08-05"))
      (libsource (lib "eagle-import") (part "EURORACK_POWERSMT"))
    )
    (comp (ref "FB1")
      (value "FB")
      (footprint "eagle-import:WUERTH-ELEKTRONIK_0603")
      (fields (field (name "MPN") "MI0603J601R-10"))
      (libsource (lib "eagle-import") (part "FERRITE_BEAD_0603"))
    )
    (comp (ref "FB2")
      (value "FB")
      (footprint "eagle-import:WUERTH-ELEKTRONIK_0603")
      (fields (field (name "MPN") "MI0603J601R-10"))
      (libsource (lib "eagle-import") (part "FERRITE_BEAD_0603"))
    )
    (comp (ref "FB3")
      (value "FB")
      (footprint "eagle-import:WUERTH-ELEKTRONIK_0603")
      (fields (field (name "MPN") "MI0603J601R-10"))
      (libsource (lib "eagle-import") (part "FERRITE_BEAD_0603"))
    )
    (comp (ref "L1")
      (value "2.2uH")
      (footprint "eagle-import:BOURNS_SRP2010")
      (libsource (lib "eagle-import") (part "INDUCTORS"))
    )
    (comp (ref "L2")
      (value "2.2uH")
      (footprint "eagle-import:BOURNS_SRP2010")
      (libsource (lib "eagle-import") (part "INDUCTORS"))
    )
    (comp (ref "L3")
      (value "47UH")
      (footprint "eagle-import:SRN3015TA")
      (libsource (lib "eagle-import") (part "SRN3015TA"))
    )
    (comp (ref "R62")
      (value "10R")
      (footprint "eagle-import:R0603")
      (libsource (lib "eagle-import") (part "R-US_R0603"))
    )
    (comp (ref "R65")
      (value "10R")
      (footprint "eagle-import:R0603")
      (libsource (lib "eagle-import") (part "R-US_R0603"))
    )
    (comp (ref "R68")
      (value "10R")
      (footprint "eagle-import:R0603")
      (libsource (lib "eagle-import") (part "R-US_R0603"))
    )
    (comp (ref "R69")
      (value "10R")
      (footprint "eagle-import:R0603")
      (libsource (lib "eagle-import") (part "R-US_R0603"))
    )
    (comp (ref "U$1")
      (value "POWER_ISOLATE")
      (footprint "eagle-import:XP_POWER_ISEXXXXA")
      (fields (field (name "MPN") "ISE2405A"))
      (libsource (lib "eagle-import") (part "POWER_ISOLATE"))
    )
    (comp (ref "U1")
      (value "AP1509-33SG-13")
      (footprint "eagle-import:SO-8")
      (libsource (lib "eagle-import") (part "AP1509-3V3"))
    )
    (comp (ref "U_OLED")
      (value "OLED_DISPLAY")
      (footprint "eagle-import:ER-OLEDM015-2")
      (fields (field (name "MPN") "ER-OLEDM015-2W-SPI-I2C"))
      (libsource (lib "eagle-import") (part "OLED_DISPLAY"))
    )
  )
  (nets
    (net (code "1") (name "+3V3_A") (class "Default")
      (node (ref "C1") (pin "1") (pinfunction "1_1") (pintype "passive"))
      (node (ref "C14") (pin "1") (pinfunction "1_1") (pintype "passive"))
      (node (ref "C4") (pin "1") (pinfunction "1_1") (pintype "passive"))
      (node (ref "R19") (pin "1") (pinfunction "1_1") (pintype "passive"))
      (node (ref "U2") (pin "12") (pinfunction "CSK3_12") (pintype "bidirectional"))
      (node (ref "U2") (pin "4") (pinfunction "VA_4") (pintype "bidirectional"))
      (node (ref "U2") (pin "6") (pinfunction "DEM0_6") (pintype "bidirectional"))
      (node (ref "U7") (pin "4") (pinfunction "V+_4") (pintype "power_in"))
      (node (ref "U_DAISY") (pin "21") (pinfunction "+3V3_A_21") (pintype "bidirectional"))
      (node (ref "U_DAISY") (pin "B21") (pinfunction "+3V3_A_B21") (pintype "bidirectional"))
      (node (ref "VR_1") (pin "3") (pinfunction "3_3") (pintype "passive"))
      (node (ref "VR_2") (pin "3") (pinfunction "3_3") (pintype "passive"))
      (node (ref "VR_3") (pin "3") (pinfunction "3_3") (pintype "passive"))
      (node (ref "VR_4") (pin "3") (pinfunction "3_3") (pintype "passive"))
    )
    (net (code "2") (name "+3V3_D") (class "Default")
      (node (ref "C16") (pin "1") (pinfunction "1_1") (pintype "passive"))
      (node (ref "R1") (pin "1") (pinfunction "1_1") (pintype "passive"))
      (node (ref "R29") (pin "2") (pinfunction "2_2") (pintype "passive"))
      (node (ref "R3") (pin "2") (pinfunction "2_2") (pintype "passive"))
      (node (ref "R36") (pin "2") (pinfunction "2_2") (pintype "passive"))
      (node (ref "R4") (pin "2") (pinfunction "2_2") (pintype "passive"))
      (node (ref "R5") (pin "2") (pinfunction "2_2") (pintype "passive"))
      (node (ref "R6") (pin "2") (pinfunction "2_2") (pintype "passive"))
      (node (ref "R64") (pin "1") (pinfunction "1_1") (pintype "passive"))
      (node (ref "R7") (pin "2") (pinfunction "2_2") (pintype "passive"))
      (node (ref "U15") (pin "6") (pinfunction "V_6") (pintype "bidirectional"))
      (node (ref "U3") (pin "P$4") (pinfunction "VCC_P$4") (pintype "bidirectional"))
      (node (ref "U_DAISY") (pin "38") (pinfunction "+3V3_D_38") (pintype "bidirectional"))
      (node (ref "U_DAISY") (pin "B38") (pinfunction "+3V3_D_B38") (pintype "bidirectional"))
    )
    (net (code "3") (name "+3V3_OLED") (class "Default")
      (node (ref "C31") (pin "1") (pinfunction "1_1") (pintype "passive"))
      (node (ref "L3") (pin "P$2") (pinfunction "P$2_P$2") (pintype "bidirectional"))
      (node (ref "U1") (pin "3") (pinfunction "FB_3") (pintype "bidirectional"))
      (node (ref "U_OLED") (pin "2") (pinfunction "VCC_2") (pintype "bidirectional"))
    )
    (net (code "4") (name "+5V_ISOL") (class "Default")
      (node (ref "C42") (pin "+") (pinfunction "POS_+") (pintype "passive"))
      (node (ref "C43") (pin "2") (pinfunction "2_2") (pintype "passive"))
      (node (ref "FB1") (pin "2") (pinfunction "2_2") (pintype "passive"))
      (node (ref "U_DAISY") (pin "39") (pinfunction "V_IN_39") (pintype "bidirectional"))
      (node (ref "U_DAISY") (pin "B39") (pinfunction "V_IN_B39") (pintype "bidirectional"))
    )
    (net (code "5") (name "+12V") (class "Default")
      (node (ref "C20") (pin "1") (pinfunction "1_1") (pintype "passive"))
      (node (ref "C22") (pin "1") (pinfunction "1_1") (pintype "passive"))
      (node (ref "C29") (pin "1") (pinfunction "1_1") (pintype "passive"))
      (node (ref "C33") (pin "1") (pinfunction "1_1") (pintype "passive"))
      (node (ref "C34") (pin "1") (pinfunction "1_1") (pintype "passive"))
      (node (ref "C36") (pin "1") (pinfunction "1_1") (pintype "passive"))
      (node (ref "C44") (pin "1") (pinfunction "1_1") (pintype "passive"))
      (node (ref "C50") (pin "1") (pinfunction "1_1") (pintype "passive"))
      (node (ref "C9") (pin "1") (pinfunction "1_1") (pintype "passive"))
      (node (ref "D1") (pin "C") (pinfunction "C_C") (pintype "passive"))
      (node (ref "R62") (pin "1") (pinfunction "1_1") (pintype "passive"))
      (node (ref "R65") (pin "1") (pinfunction "1_1") (pintype "passive"))
      (node (ref "U1") (pin "1") (pinfunction "VIN_1") (pintype "bidirectional"))
      (node (ref "U11") (pin "4") (pinfunction "V+_4") (pintype "power_in"))
      (node (ref "U13") (pin "4") (pinfunction "V+_4") (pintype "power_in"))
      (node (ref "U14") (pin "4") (pinfunction "V+_4") (pintype "power_in"))
      (node (ref "U16") (pin "4") (pinfunction "V+_4") (pintype "power_in"))
      (node (ref "U4") (pin "4") (pinfunction "V+_4") (pintype "power_in"))
      (node (ref "U5") (pin "4") (pinfunction "V+_4") (pintype "power_in"))
    )
    (net (code "6") (name "-10V_REF") (class "Default")
      (node (ref "C13") (pin "1") (pinfunction "1_1") (pintype "passive"))
      (node (ref "R106") (pin "1") (pinfunction "1_1") (pintype "passive"))
      (node (ref "R18") (pin "1") (pinfunction "1_1") (pintype "passive"))
      (node (ref "R23") (pin "1") (pinfunction "1_1") (pintype "passive"))
      (node (ref "R26") (pin "1") (pinfunction "1_1") (pintype "passive"))
      (node (ref "R31") (pin "1") (pinfunction "1_1") (pintype "passive"))
      (node (ref "U6") (pin "2") (pinfunction "A_2") (pintype "passive"))
    )
    (net (code "7") (name "-12V") (class "Default")
      (node (ref "C10") (pin "2") (pinfunction "2_2") (pintype "passive"))
      (node (ref "C21") (pin "2") (pinfunction "2_2") (pintype "passive"))
      (node (ref "C23") (pin "2") (pinfunction "2_2") (pintype "passive"))
      (node (ref "C30") (pin "2") (pinfunction "2_2") (pintype "passive"))
      (node (ref "C35") (pin "2") (pinfunction "2_2") (pintype "passive"))
      (node (ref "C37") (pin "2") (pinfunction "2_2") (pintype "passive"))
      (node (ref "C45") (pin "2") (pinfunction "2_2") (pintype "passive"))
      (node (ref "C51") (pin "2") (pinfunction "2_2") (pintype "passive"))
      (node (ref "D2") (pin "A") (pinfunction "A_A") (pintype "passive"))
      (node (ref "R18") (pin "2") (pinfunction "2_2") (pintype "passive"))
      (node (ref "R68") (pin "1") (pinfunction "1_1") (pintype "passive"))
      (node (ref "R69") (pin "1") (pinfunction "1_1") (pintype "passive"))
      (node (ref "U11") (pin "11") (pinfunction "V-_11") (pintype "power_in"))
      (node (ref "U13") (pin "11") (pinfunction "V-_11") (pintype "power_in"))
      (node (ref "U14") (pin "11") (pinfunction "V-_11") (pintype "power_in"))
      (node (ref "U16") (pin "11") (pinfunction "V-_11") (pintype "power_in"))
      (node (ref "U4") (pin "11") (pinfunction "V-_11") (pintype "power_in"))
      (node (ref "U5") (pin "11") (pinfunction "V-_11") (pintype "power_in"))
    )
    (net (code "8") (name "ADC_CTRL_1") (class "Default")
      (node (ref "C54") (pin "2") (pinfunction "2_2") (pintype "passive"))
      (node (ref "R105") (pin "2") (pinfunction "2_2") (pintype "passive"))
      (node (ref "U7") (pin "8") (pinfunction "OUT_8") (pintype "output"))
      (node (ref "U_DAISY") (pin "22") (pinfunction "GPIO15(ADC0)_22") (pintype "bidirectional"))
      (node (ref "U_DAISY") (pin "B22") (pinfunction "GPIO15(ADC0)_B22") (pintype "bidirectional"))
    )
    (net (code "9") (name "ADC_CTRL_2") (class "Default")
      (node (ref "C11") (pin "2") (pinfunction "2_2") (pintype "passive"))
      (node (ref "R22") (pin "2") (pinfunction "2_2") (pintype "passive"))
      (node (ref "U7") (pin "7") (pinfunction "OUT_7") (pintype "output"))
      (node (ref "U_DAISY") (pin "23") (pinfunction "GPIO16(ADC1)_23") (pintype "bidirectional"))
      (node (ref "U_DAISY") (pin "B23") (pinfunction "GPIO16(ADC1)_B23") (pintype "bidirectional"))
    )
    (net (code "10") (name "ADC_CTRL_3") (class "Default")
      (node (ref "C12") (pin "2") (pinfunction "2_2") (pintype "passive"))
      (node (ref "R25") (pin "2") (pinfunction "2_2") (pintype "passive"))
      (node (ref "U7") (pin "1") (pinfunction "OUT_1") (pintype "output"))
      (node (ref "U_DAISY") (pin "28") (pinfunction "GPIO21(ADC6)_28") (pintype "bidirectional"))
      (node (ref "U_DAISY") (pin "B28") (pinfunction "GPIO21(ADC6)_B28") (pintype "bidirectional"))
    )
    (net (code "11") (name "ADC_CTRL_4") (class "Default")
      (node (ref "C15") (pin "2") (pinfunction "2_2") (pintype "passive"))
      (node (ref "R33") (pin "2") (pinfunction "2_2") (pintype "passive"))
      (node (ref "U7") (pin "14") (pinfunction "OUT_14") (pintype "output"))
      (node (ref "U_DAISY") (pin "25") (pinfunction "GPIO18(ADC3)_25") (pintype "bidirectional"))
      (node (ref "U_DAISY") (pin "B25") (pinfunction "GPIO18(ADC3)_B25") (pintype "bidirectional"))
    )
    (net (code "12") (name "AK4556_RST") (class "Default")
      (node (ref "U2") (pin "17") (pinfunction "PDN_17") (pintype "bidirectional"))
      (node (ref "U_DAISY") (pin "36") (pinfunction "GPIO29(USB_HS_D_-)_36") (pintype "bidirectional"))
      (node (ref "U_DAISY") (pin "B36") (pinfunction "GPIO29(USB_HS_D_-)_B36") (pintype "bidirectional"))
    )
    (net (code "13") (name "AUDIO_IN_1") (class "Default")
      (node (ref "J_AUDIO_IN_1") (pin "TIP") (pinfunction "TIP_TIP") (pintype "passive"))
      (node (ref "J_AUDIO_IN_2") (pin "NORM") (pinfunction "NORM_NORM") (pintype "passive"))
      (node (ref "R55") (pin "1") (pinfunction "1_1") (pintype "passive"))
    )
    (net (code "14") (name "AUDIO_IN_2") (class "Default")
      (node (ref "J_AUDIO_IN_2") (pin "TIP") (pinfunction "TIP_TIP") (pintype "passive"))
      (node (ref "J_AUDIO_IN_3") (pin "NORM") (pinfunction "NORM_NORM") (pintype "passive"))
      (node (ref "R60") (pin "1") (pinfunction "1_1") (pintype "passive"))
    )
    (net (code "15") (name "AUDIO_IN_3") (class "Default")
      (node (ref "J_AUDIO_IN_3") (pin "TIP") (pinfunction "TIP_TIP") (pintype "passive"))
      (node (ref "J_AUDIO_IN_4") (pin "NORM") (pinfunction "NORM_NORM") (pintype "passive"))
      (node (ref "R20") (pin "1") (pinfunction "1_1") (pintype "passive"))
    )
    (net (code "16") (name "AUDIO_IN_4") (class "Default")
      (node (ref "J_AUDIO_IN_4") (pin "TIP") (pinfunction "TIP_TIP") (pintype "passive"))
      (node (ref "R40") (pin "1") (pinfunction "1_1") (pintype "passive"))
    )
    (net (code "17") (name "AUDIO_OUT_1") (class "Default")
      (node (ref "J_AUDIO_OUT_1") (pin "TIP") (pinfunction "TIP_TIP") (pintype "passive"))
      (node (ref "R67") (pin "2") (pinfunction "2_2") (pintype "passive"))
    )
    (net (code "18") (name "AUDIO_OUT_2") (class "Default")
      (node (ref "J_AUDIO_OUT_2") (pin "TIP") (pinfunction "TIP_TIP") (pintype "passive"))
      (node (ref "R72") (pin "2") (pinfunction "2_2") (pintype "passive"))
    )
    (net (code "19") (name "AUDIO_OUT_3") (class "Default")
      (node (ref "J_AUDIO_OUT_3") (pin "TIP") (pinfunction "TIP_TIP") (pintype "passive"))
      (node (ref "R49") (pin "2") (pinfunction "2_2") (pintype "passive"))
    )
    (net (code "20") (name "AUDIO_OUT_4") (class "Default")
      (node (ref "J_AUDIO_OUT_4") (pin "TIP") (pinfunction "TIP_TIP") (pintype "passive"))
      (node (ref "R51") (pin "2") (pinfunction "2_2") (pintype "passive"))
    )
    (net (code "21") (name "CV_IN_1") (class "Default")
      (node (ref "J_CV_1") (pin "TIP") (pinfunction "TIP_TIP") (pintype "passive"))
      (node (ref "R107") (pin "1") (pinfunction "1_1") (pintype "passive"))
    )
    (net (code "22") (name "CV_IN_2") (class "Default")
      (node (ref "J_CV_2") (pin "TIP") (pinfunction "TIP_TIP") (pintype "passive"))
      (node (ref "R24") (pin "1") (pinfunction "1_1") (pintype "passive"))
    )
    (net (code "23") (name "CV_IN_3") (class "Default")
      (node (ref "J_CV_3") (pin "TIP") (pinfunction "TIP_TIP") (pintype "passive"))
      (node (ref "R27") (pin "1") (pinfunction "1_1") (pintype "passive"))
    )
    (net (code "24") (name "CV_IN_4") (class "Default")
      (node (ref "J_CV_4") (pin "TIP") (pinfunction "TIP_TIP") (pintype "passive"))
      (node (ref "R32") (pin "1") (pinfunction "1_1") (pintype "passive"))
    )
    (net (code "25") (name "DAC1_OUT1") (class "Default")
      (node (ref "R8") (pin "2") (pinfunction "2_2") (pintype "passive"))
      (node (ref "U_DAISY") (pin "30") (pinfunction "GPIO23(ADC8/DAC1)_30") (pintype "bidirectional"))
      (node (ref "U_DAISY") (pin "B30") (pinfunction "GPIO23(ADC8/DAC1)_B30") (pintype "bidirectional"))
    )
    (net (code "26") (name "DAC1_OUT1_") (class "Default")
      (node (ref "J_CV_OUT_1") (pin "TIP") (pinfunction "TIP_TIP") (pintype "passive"))
      (node (ref "R12") (pin "1") (pinfunction "1_1") (pintype "passive"))
    )
    (net (code "27") (name "DAC1_OUT2") (class "Default")
      (node (ref "R10") (pin "2") (pinfunction "2_2") (pintype "passive"))
      (node (ref "U_DAISY") (pin "29") (pinfunction "GPIO22(ADC7/DAC2)_29") (pintype "bidirectional"))
      (node (ref "U_DAISY") (pin "B29") (pinfunction "GPIO22(ADC7/DAC2)_B29") (pintype "bidirectional"))
    )
    (net (code "28") (name "DAC1_OUT2_") (class "Default")
      (node (ref "J_CV_OUT_2") (pin "TIP") (pinfunction "TIP_TIP") (pintype "passive"))
      (node (ref "R13") (pin "1") (pinfunction "1_1") (pintype "passive"))
    )
    (net (code "29") (name "ENC_A") (class "Default")
      (node (ref "ENC_1") (pin "B") (pinfunction "B_B") (pintype "passive"))
      (node (ref "U_DAISY") (pin "13") (pinfunction "GPIO12(I2C1_SDA)_13") (pintype "bidirectional"))
      (node (ref "U_DAISY") (pin "B13") (pinfunction "GPIO12(I2C1_SDA)_B13") (pintype "bidirectional"))
    )
    (net (code "30") (name "ENC_B") (class "Default")
      (node (ref "ENC_1") (pin "A") (pinfunction "A_A") (pintype "passive"))
      (node (ref "U_DAISY") (pin "12") (pinfunction "GPIO11(I2C1_SCL)_12") (pintype "bidirectional"))
      (node (ref "U_DAISY") (pin "B12") (pinfunction "GPIO11(I2C1_SCL)_B12") (pintype "bidirectional"))
    )
    (net (code "31") (name "ENC_CLICK") (class "Default")
      (node (ref "ENC_1") (pin "E") (pinfunction "2_E") (pintype "passive"))
      (node (ref "U_DAISY") (pin "1") (pinfunction "GPIO0(USB_HS_ID)_1") (pintype "bidirectional"))
      (node (ref "U_DAISY") (pin "B1") (pinfunction "GPIO0(USB_HS_ID)_B1") (pintype "bidirectional"))
    )
    (net (code "32") (name "EXT_AUDIO_IN_L") (class "Default")
      (node (ref "C40") (pin "2") (pinfunction "2_2") (pintype "passive"))
      (node (ref "U2") (pin "2") (pinfunction "LIN_2") (pintype "bidirectional"))
    )
    (net (code "33") (name "EXT_AUDIO_IN_R") (class "Default")
      (node (ref "C41") (pin "2") (pinfunction "2_2") (pintype "passive"))
      (node (ref "U2") (pin "1") (pinfunction "RIN_1") (pintype "bidirectional"))
    )
    (net (code "34") (name "EXT_AUDIO_OUT_L") (class "Default")
      (node (ref "C55") (pin "1") (pinfunction "1_1") (pintype "passive"))
      (node (ref "U2") (pin "19") (pinfunction "LOU_19") (pintype "bidirectional"))
    )
    (net (code "35") (name "EXT_AUDIO_OUT_R") (class "Default")
      (node (ref "C56") (pin "1") (pinfunction "1_1") (pintype "passive"))
      (node (ref "U2") (pin "20") (pinfunction "ROU_20") (pintype "bidirectional"))
    )
    (net (code "36") (name "GATE_IN_1") (class "Default")
      (node (ref "R30") (pin "1") (pinfunction "1_1") (pintype "passive"))
      (node (ref "U_DAISY") (pin "27") (pinfunction "GPIO20(ADC5)_27") (pintype "bidirectional"))
      (node (ref "U_DAISY") (pin "B27") (pinfunction "GPIO20(ADC5)_B27") (pintype "bidirectional"))
    )
    (net (code "37") (name "GATE_IN_2") (class "Default")
      (node (ref "R37") (pin "1") (pinfunction "1_1") (pintype "passive"))
      (node (ref "U_DAISY") (pin "26") (pinfunction "GPIO19(ADC4)_26") (pintype "bidirectional"))
      (node (ref "U_DAISY") (pin "B26") (pinfunction "GPIO19(ADC4)_B26") (pintype "bidirectional"))
    )
    (net (code "38") (name "GATE_OUT") (class "Default")
      (node (ref "R112") (pin "2") (pinfunction "2_2") (pintype "passive"))
      (node (ref "U_DAISY") (pin "24") (pinfunction "GPIO17(ADC2)_24") (pintype "bidirectional"))
      (node (ref "U_DAISY") (pin "B24") (pinfunction "GPIO17(ADC2)_B24") (pintype "bidirectional"))
    )
    (net (code "39") (name "GND") (class "Default")
      (node (ref "C1") (pin "2") (pinfunction "2_2") (pintype "passive"))
      (node (ref "C10") (pin "1") (pinfunction "1_1") (pintype "passive"))
      (node (ref "C13") (pin "2") (pinfunction "2_2") (pintype "passive"))
      (node (ref "C14") (pin "2") (pinfunction "2_2") (pintype "passive"))
      (node (ref "C16") (pin "2") (pinfunction "2_2") (pintype "passive"))
      (node (ref "C2") (pin "2") (pinfunction "2_2") (pintype "passive"))
      (node (ref "C20") (pin "2") (pinfunction "2_2") (pintype "passive"))
      (node (ref "C21") (pin "1") (pinfunction "1_1") (pintype "passive"))
      (node (ref "C22") (pin "2") (pinfunction "2_2") (pintype "passive"))
      (node (ref "C23") (pin "1") (pinfunction "1_1") (pintype "passive"))
      (node (ref "C29") (pin "2") (pinfunction "2_2") (pintype "passive"))
      (node (ref "C3") (pin "2") (pinfunction "2_2") (pintype "passive"))
      (node (ref "C30") (pin "1") (pinfunction "1_1") (pintype "passive"))
      (node (ref "C31") (pin "2") (pinfunction "2_2") (pintype "passive"))
      (node (ref "C33") (pin "2") (pinfunction "2_2") (pintype "passive"))
      (node (ref "C34") (pin "2") (pinfunction "2_2") (pintype "passive"))
      (node (ref "C35") (pin "1") (pinfunction "1_1") (pintype "passive"))
      (node (ref "C36") (pin "2") (pinfunction "2_2") (pintype "passive"))
      (node (ref "C37") (pin "1") (pinfunction "1_1") (pintype "passive"))
      (node (ref "C39") (pin "1") (pinfunction "1_1") (pintype "passive"))
      (node (ref "C4") (pin "2") (pinfunction "2_2") (pintype "passive"))
      (node (ref "C42") (pin "-") (pinfunction "NEG_-") (pintype "passive"))
      (node (ref "C43") (pin "1") (pinfunction "1_1") (pintype "passive"))
      (node (ref "C44") (pin "2") (pinfunction "2_2") (pintype "passive"))
      (node (ref "C45") (pin "1") (pinfunction "1_1") (pintype "passive"))
      (node (ref "C5") (pin "1") (pinfunction "1_1") (pintype "passive"))
      (node (ref "C50") (pin "2") (pinfunction "2_2") (pintype "passive"))
      (node (ref "C51") (pin "1") (pinfunction "1_1") (pintype "passive"))
      (node (ref "C8") (pin "1") (pinfunction "1_1") (pintype "passive"))
      (node (ref "C9") (pin "2") (pinfunction "2_2") (pintype "passive"))
      (node (ref "D3") (pin "A") (pinfunction "A_A") (pintype "passive"))
      (node (ref "ENC_1") (pin "C") (pinfunction "C_C") (pintype "passive"))
      (node (ref "ENC_1") (pin "D") (pinfunction "1_D") (pintype "passive"))
      (node (ref "EP1") (pin "GND1A") (pinfunction "GND_GND1A") (pintype "bidirectional"))
      (node (ref "EP1") (pin "GND1B") (pinfunction "GND_GND1B") (pintype "bidirectional"))
      (node (ref "EP1") (pin "GND2A") (pinfunction "GND_GND2A") (pintype "bidirectional"))
      (node (ref "EP1") (pin "GND2B") (pinfunction "GND_GND2B") (pintype "bidirectional"))
      (node (ref "EP1") (pin "GND3A") (pinfunction "GND_GND3A") (pintype "bidirectional"))
      (node (ref "EP1") (pin "GND3B") (pinfunction "GND_GND3B") (pintype "bidirectional"))
      (node (ref "J_AUDIO_IN_1") (pin "GND") (pinfunction "GND_GND") (pintype "passive"))
      (node (ref "J_AUDIO_IN_2") (pin "GND") (pinfunction "GND_GND") (pintype "passive"))
      (node (ref "J_AUDIO_IN_3") (pin "GND") (pinfunction "GND_GND") (pintype "passive"))
      (node (ref "J_AUDIO_IN_4") (pin "GND") (pinfunction "GND_GND") (pintype "passive"))
      (node (ref "J_AUDIO_OUT_1") (pin "GND") (pinfunction "GND_GND") (pintype "passive"))
      (node (ref "J_AUDIO_OUT_2") (pin "GND") (pinfunction "GND_GND") (pintype "passive"))
      (node (ref "J_AUDIO_OUT_3") (pin "GND") (pinfunction "GND_GND") (pintype "passive"))
      (node (ref "J_AUDIO_OUT_4") (pin "GND") (pinfunction "GND_GND") (pintype "passive"))
      (node (ref "J_CV_1") (pin "GND") (pinfunction "GND_GND") (pintype "passive"))
      (node (ref "J_CV_2") (pin "GND") (pinfunction "GND_GND") (pintype "passive"))
      (node (ref "J_CV_3") (pin "GND") (pinfunction "GND_GND") (pintype "passive"))
      (node (ref "J_CV_4") (pin "GND") (pinfunction "GND_GND") (pintype "passive"))
      (node (ref "J_CV_OUT_1") (pin "GND") (pinfunction "GND_GND") (pintype "passive"))
      (node (ref "J_CV_OUT_2") (pin "GND") (pinfunction "GND_GND") (pintype "passive"))
      (node (ref "J_GATE_IN_1") (pin "GND") (pinfunction "GND_GND") (pintype "passive"))
      (node (ref "J_GATE_IN_2") (pin "GND") (pinfunction "GND_GND") (pintype "passive"))
      (node (ref "J_GATE_OUT") (pin "GND") (pinfunction "GND_GND") (pintype "passive"))
      (node (ref "J_MIDI_IN") (pin "GND") (pinfunction "GND_GND") (pintype "passive"))
      (node (ref "J_MIDI_OUT") (pin "GND") (pinfunction "GND_GND") (pintype "passive"))
      (node (ref "Q1") (pin "E") (pinfunction "E_E") (pintype "passive"))
      (node (ref "Q2") (pin "E") (pinfunction "E_E") (pintype "passive"))
      (node (ref "R28") (pin "1") (pinfunction "1_1") (pintype "passive"))
      (node (ref "R35") (pin "1") (pinfunction "1_1") (pintype "passive"))
      (node (ref "R85") (pin "1") (pinfunction "1_1") (pintype "passive"))
      (node (ref "R86") (pin "1") (pinfunction "1_1") (pintype "passive"))
      (node (ref "U$1") (pin "P$4") (pinfunction "OUT-_P$4") (pintype "bidirectional"))
      (node (ref "U1") (pin "4") (pinfunction "SD_4") (pintype "bidirectional"))
      (node (ref "U1") (pin "5") (pinfunction "GND_5") (pintype "bidirectional"))
      (node (ref "U1") (pin "6") (pinfunction "GND_6") (pintype "bidirectional"))
      (node (ref "U1") (pin "7") (pinfunction "GND_7") (pintype "bidirectional"))
      (node (ref "U1") (pin "8") (pinfunction "GND_8") (pintype "bidirectional"))
      (node (ref "U11") (pin "10") (pinfunction "+IN_10") (pintype "input"))
      (node (ref "U11") (pin "12") (pinfunction "+IN_12") (pintype "input"))
      (node (ref "U11") (pin "3") (pinfunction "+IN_3") (pintype "input"))
      (node (ref "U11") (pin "5") (pinfunction "+IN_5") (pintype "input"))
      (node (ref "U13") (pin "10") (pinfunction "+IN_10") (pintype "input"))
      (node (ref "U13") (pin "12") (pinfunction "+IN_12") (pintype "input"))
      (node (ref "U13") (pin "3") (pinfunction "+IN_3") (pintype "input"))
      (node (ref "U13") (pin "5") (pinfunction "+IN_5") (pintype "input"))
      (node (ref "U14") (pin "10") (pinfunction "+IN_10") (pintype "input"))
      (node (ref "U14") (pin "12") (pinfunction "+IN_12") (pintype "input"))
      (node (ref "U14") (pin "3") (pinfunction "+IN_3") (pintype "input"))
      (node (ref "U14") (pin "5") (pinfunction "+IN_5") (pintype "input"))
      (node (ref "U15") (pin "5") (pinfunction "GND_5") (pintype "bidirectional"))
      (node (ref "U16") (pin "10") (pinfunction "+IN_10") (pintype "input"))
      (node (ref "U16") (pin "12") (pinfunction "+IN_12") (pintype "input"))
      (node (ref "U16") (pin "3") (pinfunction "+IN_3") (pintype "input"))
      (node (ref "U16") (pin "5") (pinfunction "+IN_5") (pintype "input"))
      (node (ref "U2") (pin "10") (pinfunction "CSK1_10") (pintype "bidirectional"))
      (node (ref "U2") (pin "11") (pinfunction "CSK2_11") (pintype "bidirectional"))
      (node (ref "U2") (pin "3") (pinfunction "GND_3") (pintype "bidirectional"))
      (node (ref "U2") (pin "7") (pinfunction "DEM1_7") (pintype "bidirectional"))
      (node (ref "U2") (pin "9") (pinfunction "CSK0_9") (pintype "bidirectional"))
      (node (ref "U3") (pin "GND1") (pinfunction "SHIELD_GND1") (pintype "bidirectional"))
      (node (ref "U3") (pin "GND2") (pinfunction "SHIELD_GND2") (pintype "bidirectional"))
      (node (ref "U3") (pin "P$6") (pinfunction "GND_P$6") (pintype "bidirectional"))
      (node (ref "U4") (pin "10") (pinfunction "+IN_10") (pintype "input"))
      (node (ref "U4") (pin "12") (pinfunction "+IN_12") (pintype "input"))
      (node (ref "U4") (pin "3") (pinfunction "+IN_3") (pintype "input"))
      (node (ref "U4") (pin "5") (pinfunction "+IN_5") (pintype "input"))
      (node (ref "U5") (pin "10") (pinfunction "+IN_10") (pintype "input"))
      (node (ref "U5") (pin "12") (pinfunction "+IN_12") (pintype "input"))
      (node (ref "U5") (pin "3") (pinfunction "+IN_3") (pintype "input"))
      (node (ref "U5") (pin "5") (pinfunction "+IN_5") (pintype "input"))
      (node (ref "U6") (pin "1") (pinfunction "C_1") (pintype "passive"))
      (node (ref "U7") (pin "10") (pinfunction "+IN_10") (pintype "input"))
      (node (ref "U7") (pin "11") (pinfunction "V-_11") (pintype "power_in"))
      (node (ref "U7") (pin "12") (pinfunction "+IN_12") (pintype "input"))
      (node (ref "U7") (pin "3") (pinfunction "+IN_3") (pintype "input"))
      (node (ref "U7") (pin "5") (pinfunction "+IN_5") (pintype "input"))
      (node (ref "U_DAISY") (pin "20") (pinfunction "AGND_20") (pintype "bidirectional"))
      (node (ref "U_DAISY") (pin "40") (pinfunction "GND_40") (pintype "bidirectional"))
      (node (ref "U_DAISY") (pin "B20") (pinfunction "AGND_B20") (pintype "bidirectional"))
      (node (ref "U_DAISY") (pin "B40") (pinfunction "GND_B40") (pintype "bidirectional"))
      (node (ref "U_OLED") (pin "1") (pinfunction "GND_1") (pintype "bidirectional"))
      (node (ref "VR_1") (pin "1") (pinfunction "1_1") (pintype "passive"))
      (node (ref "VR_2") (pin "1") (pinfunction "1_1") (pintype "passive"))
      (node (ref "VR_3") (pin "1") (pinfunction "1_1") (pintype "passive"))
      (node (ref "VR_4") (pin "1") (pinfunction "1_1") (pintype "passive"))
    )
    (net (code "40") (name "INT_AUDIO_IN_L") (class "Default")
      (node (ref "R82") (pin "2") (pinfunction "2_2") (pintype "passive"))
      (node (ref "U_DAISY") (pin "16") (pinfunction "AUDIO_IN_L_16") (pintype "bidirectional"))
      (node (ref "U_DAISY") (pin "B16") (pinfunction "AUDIO_IN_L_B16") (pintype "bidirectional"))
    )
    (net (code "41") (name "INT_AUDIO_IN_R") (class "Default")
      (node (ref "R98") (pin "2") (pinfunction "2_2") (pintype "passive"))
      (node (ref "U_DAISY") (pin "17") (pinfunction "AUDIO_IN_R_17") (pintype "bidirectional"))
      (node (ref "U_DAISY") (pin "B17") (pinfunction "AUDIO_IN_R_B17") (pintype "bidirectional"))
    )
    (net (code "42") (name "INT_AUDIO_OUT_L") (class "Default")
      (node (ref "R102") (pin "1") (pinfunction "1_1") (pintype "passive"))
      (node (ref "U_DAISY") (pin "18") (pinfunction "AUDIO_OUT_L_18") (pintype "bidirectional"))
      (node (ref "U_DAISY") (pin "B18") (pinfunction "AUDIO_OUT_L_B18") (pintype "bidirectional"))
    )
    (net (code "43") (name "INT_AUDIO_OUT_R") (class "Default")
      (node (ref "R104") (pin "1") (pinfunction "1_1") (pintype "passive"))
      (node (ref "U_DAISY") (pin "19") (pinfunction "AUDIO_OUT_R_19") (pintype "bidirectional"))
      (node (ref "U_DAISY") (pin "B19") (pinfunction "AUDIO_OUT_R_B19") (pintype "bidirectional"))
    )
    (net (code "44") (name "KNOB_1") (class "Default")
      (node (ref "R108") (pin "1") (pinfunction "1_1") (pintype "passive"))
      (node (ref "VR_1") (pin "2") (pinfunction "2_2") (pintype "passive"))
    )
    (net (code "45") (name "KNOB_2") (class "Default")
      (node (ref "R109") (pin "1") (pinfunction "1_1") (pintype "passive"))
      (node (ref "VR_2") (pin "2") (pinfunction "2_2") (pintype "passive"))
    )
    (net (code "46") (name "KNOB_3") (class "Default")
      (node (ref "R110") (pin "1") (pinfunction "1_1") (pintype "passive"))
      (node (ref "VR_3") (pin "2") (pinfunction "2_2") (pintype "passive"))
    )
    (net (code "47") (name "KNOB_4") (class "Default")
      (node (ref "R111") (pin "1") (pinfunction "1_1") (pintype "passive"))
      (node (ref "VR_4") (pin "2") (pinfunction "2_2") (pintype "passive"))
    )
    (net (code "48") (name "MIDI_IN_A") (class "Default")
      (node (ref "R63") (pin "2") (pinfunction "2_2") (pintype "passive"))
      (node (ref "R78") (pin "1") (pinfunction "1_1") (pintype "passive"))
      (node (ref "R79") (pin "1") (pinfunction "1_1") (pintype "passive"))
    )
    (net (code "49") (name "MIDI_IN_B") (class "Default")
      (node (ref "D5") (pin "A") (pinfunction "A_A") (pintype "passive"))
      (node (ref "R83") (pin "1") (pinfunction "1_1") (pintype "passive"))
      (node (ref "R84") (pin "1") (pinfunction "1_1") (pintype "passive"))
      (node (ref "U15") (pin "2") (pinfunction "C_2") (pintype "bidirectional"))
    )
    (net (code "50") (name "MIDI_IN_RING") (class "Default")
      (node (ref "J_MIDI_IN") (pin "RING") (pinfunction "NORM_RING") (pintype "passive"))
      (node (ref "R79") (pin "2") (pinfunction "2_2") (pintype "passive"))
      (node (ref "R84") (pin "2") (pinfunction "2_2") (pintype "passive"))
    )
    (net (code "51") (name "MIDI_IN_TIP") (class "Default")
      (node (ref "J_MIDI_IN") (pin "TIP") (pinfunction "TIP_TIP") (pintype "passive"))
      (node (ref "R78") (pin "2") (pinfunction "2_2") (pintype "passive"))
      (node (ref "R83") (pin "2") (pinfunction "2_2") (pintype "passive"))
    )
    (net (code "52") (name "Net-(C38-NEG)") (class "Default")
      (node (ref "C32") (pin "1") (pinfunction "1_1") (pintype "passive"))
      (node (ref "C38") (pin "-") (pinfunction "NEG_-") (pintype "passive"))
      (node (ref "L2") (pin "P$1") (pinfunction "P$1_P$1") (pintype "bidirectional"))
      (node (ref "R68") (pin "2") (pinfunction "2_2") (pintype "passive"))
      (node (ref "R69") (pin "2") (pinfunction "2_2") (pintype "passive"))
    )
    (net (code "53") (name "Net-(C38-POS)") (class "Default")
      (node (ref "C32") (pin "2") (pinfunction "2_2") (pintype "passive"))
      (node (ref "C38") (pin "+") (pinfunction "POS_+") (pintype "passive"))
      (node (ref "L1") (pin "P$1") (pinfunction "P$1_P$1") (pintype "bidirectional"))
      (node (ref "R62") (pin "2") (pinfunction "2_2") (pintype "passive"))
      (node (ref "R65") (pin "2") (pinfunction "2_2") (pintype "passive"))
    )
    (net (code "54") (name "Net-(C40-Pad1)") (class "Default")
      (node (ref "C40") (pin "1") (pinfunction "1_1") (pintype "passive"))
      (node (ref "R46") (pin "2") (pinfunction "2_2") (pintype "passive"))
    )
    (net (code "55") (name "Net-(C41-Pad1)") (class "Default")
      (node (ref "C41") (pin "1") (pinfunction "1_1") (pintype "passive"))
      (node (ref "R47") (pin "2") (pinfunction "2_2") (pintype "passive"))
    )
    (net (code "56") (name "Net-(C55-Pad2)") (class "Default")
      (node (ref "C55") (pin "2") (pinfunction "2_2") (pintype "passive"))
      (node (ref "R57") (pin "1") (pinfunction "1_1") (pintype "passive"))
      (node (ref "R85") (pin "2") (pinfunction "2_2") (pintype "passive"))
    )
    (net (code "57") (name "Net-(C56-Pad2)") (class "Default")
      (node (ref "C56") (pin "2") (pinfunction "2_2") (pintype "passive"))
      (node (ref "R59") (pin "1") (pinfunction "1_1") (pintype "passive"))
      (node (ref "R86") (pin "2") (pinfunction "2_2") (pintype "passive"))
    )
    (net (code "58") (name "Net-(D1-PadA)") (class "Default")
      (node (ref "D1") (pin "A") (pinfunction "A_A") (pintype "passive"))
      (node (ref "FB2") (pin "2") (pinfunction "2_2") (pintype "passive"))
    )
    (net (code "59") (name "Net-(D2-PadC)") (class "Default")
      (node (ref "D2") (pin "C") (pinfunction "C_C") (pintype "passive"))
      (node (ref "FB3") (pin "2") (pinfunction "2_2") (pintype "passive"))
    )
    (net (code "60") (name "Net-(EP1-+12VIN-PadP12VA)") (class "Default")
      (node (ref "EP1") (pin "P12VA") (pinfunction "+12VIN_P12VA") (pintype "bidirectional"))
      (node (ref "EP1") (pin "P12VB") (pinfunction "+12VIN_P12VB") (pintype "bidirectional"))
      (node (ref "FB2") (pin "1") (pinfunction "1_1") (pintype "passive"))
    )
    (net (code "61") (name "Net-(EP1--12VIN-PadN12VA)") (class "Default")
      (node (ref "EP1") (pin "N12VA") (pinfunction "-12VIN_N12VA") (pintype "bidirectional"))
      (node (ref "EP1") (pin "N12VB") (pinfunction "-12VIN_N12VB") (pintype "bidirectional"))
      (node (ref "FB3") (pin "1") (pinfunction "1_1") (pintype "passive"))
    )
    (net (code "62") (name "Net-(J_GATE_IN_2-PadTIP)") (class "Default")
      (node (ref "J_GATE_IN_2") (pin "TIP") (pinfunction "TIP_TIP") (pintype "passive"))
      (node (ref "R34") (pin "1") (pinfunction "1_1") (pintype "passive"))
    )
    (net (code "63") (name "Net-(J_MIDI_OUT-NORM)") (class "Default")
      (node (ref "J_MIDI_OUT") (pin "RING") (pinfunction "NORM_RING") (pintype "passive"))
      (node (ref "R1") (pin "2") (pinfunction "2_2") (pintype "passive"))
    )
    (net (code "64") (name "Net-(J_MIDI_OUT-PadTIP)") (class "Default")
      (node (ref "J_MIDI_OUT") (pin "TIP") (pinfunction "TIP_TIP") (pintype "passive"))
      (node (ref "R2") (pin "1") (pinfunction "1_1") (pintype "passive"))
    )
    (net (code "65") (name "Net-(Q1-PadB)") (class "Default")
      (node (ref "Q1") (pin "B") (pinfunction "B_B") (pintype "passive"))
      (node (ref "R21") (pin "2") (pinfunction "2_2") (pintype "passive"))
      (node (ref "R28") (pin "2") (pinfunction "2_2") (pintype "passive"))
    )
    (net (code "66") (name "Net-(Q1-PadC)") (class "Default")
      (node (ref "Q1") (pin "C") (pinfunction "C_C") (pintype "passive"))
      (node (ref "R29") (pin "1") (pinfunction "1_1") (pintype "passive"))
      (node (ref "R30") (pin "2") (pinfunction "2_2") (pintype "passive"))
    )
    (net (code "67") (name "Net-(Q2-PadB)") (class "Default")
      (node (ref "Q2") (pin "B") (pinfunction "B_B") (pintype "passive"))
      (node (ref "R34") (pin "2") (pinfunction "2_2") (pintype "passive"))
      (node (ref "R35") (pin "2") (pinfunction "2_2") (pintype "passive"))
    )
    (net (code "68") (name "Net-(Q2-PadC)") (class "Default")
      (node (ref "Q2") (pin "C") (pinfunction "C_C") (pintype "passive"))
      (node (ref "R36") (pin "1") (pinfunction "1_1") (pintype "passive"))
      (node (ref "R37") (pin "2") (pinfunction "2_2") (pintype "passive"))
    )
    (net (code "69") (name "Net-(U$1-IN+)") (class "Default")
      (node (ref "L1") (pin "P$2") (pinfunction "P$2_P$2") (pintype "bidirectional"))
      (node (ref "U$1") (pin "P$2") (pinfunction "IN+_P$2") (pintype "bidirectional"))
    )
    (net (code "70") (name "Net-(U$1-IN-)") (class "Default")
      (node (ref "L2") (pin "P$2") (pinfunction "P$2_P$2") (pintype "bidirectional"))
      (node (ref "U$1") (pin "P$1") (pinfunction "IN-_P$1") (pintype "bidirectional"))
    )
    (net (code "71") (name "Net-(U$1-OUT+)") (class "Default")
      (node (ref "C39") (pin "2") (pinfunction "2_2") (pintype "passive"))
      (node (ref "FB1") (pin "1") (pinfunction "1_1") (pintype "passive"))
      (node (ref "U$1") (pin "P$5") (pinfunction "OUT+_P$5") (pintype "bidirectional"))
    )
    (net (code "72") (name "Net-(U1-OUT)") (class "Default")
      (node (ref "D3") (pin "C") (pinfunction "C_C") (pintype "passive"))
      (node (ref "L3") (pin "P$1") (pinfunction "P$1_P$1") (pintype "bidirectional"))
      (node (ref "U1") (pin "2") (pinfunction "OUT_2") (pintype "bidirectional"))
    )
    (net (code "73") (name "Net-(U2C-VCOM)") (class "Default")
      (node (ref "C5") (pin "2") (pinfunction "2_2") (pintype "passive"))
      (node (ref "C8") (pin "2") (pinfunction "2_2") (pintype "passive"))
      (node (ref "U2") (pin "18") (pinfunction "VCOM_18") (pintype "bidirectional"))
    )
    (net (code "74") (name "Net-(U2C-VD)") (class "Default")
      (node (ref "C2") (pin "1") (pinfunction "1_1") (pintype "passive"))
      (node (ref "C3") (pin "1") (pinfunction "1_1") (pintype "passive"))
      (node (ref "R19") (pin "2") (pinfunction "2_2") (pintype "passive"))
      (node (ref "U2") (pin "5") (pinfunction "VD_5") (pintype "bidirectional"))
    )
    (net (code "75") (name "Net-(U4A--IN)") (class "Default")
      (node (ref "C46") (pin "1") (pinfunction "1_1") (pintype "passive"))
      (node (ref "R55") (pin "2") (pinfunction "2_2") (pintype "passive"))
      (node (ref "R56") (pin "1") (pinfunction "1_1") (pintype "passive"))
      (node (ref "U4") (pin "2") (pinfunction "-IN_2") (pintype "input"))
    )
    (net (code "76") (name "Net-(U4A-OUT)") (class "Default")
      (node (ref "C46") (pin "2") (pinfunction "2_2") (pintype "passive"))
      (node (ref "R56") (pin "2") (pinfunction "2_2") (pintype "passive"))
      (node (ref "R73") (pin "1") (pinfunction "1_1") (pintype "passive"))
      (node (ref "U4") (pin "1") (pinfunction "OUT_1") (pintype "output"))
    )
    (net (code "77") (name "Net-(U4B--IN)") (class "Default")
      (node (ref "C47") (pin "1") (pinfunction "1_1") (pintype "passive"))
      (node (ref "R60") (pin "2") (pinfunction "2_2") (pintype "passive"))
      (node (ref "R61") (pin "1") (pinfunction "1_1") (pintype "passive"))
      (node (ref "U4") (pin "6") (pinfunction "-IN_6") (pintype "input"))
    )
    (net (code "78") (name "Net-(U4B-OUT)") (class "Default")
      (node (ref "C47") (pin "2") (pinfunction "2_2") (pintype "passive"))
      (node (ref "R61") (pin "2") (pinfunction "2_2") (pintype "passive"))
      (node (ref "R80") (pin "1") (pinfunction "1_1") (pintype "passive"))
      (node (ref "U4") (pin "7") (pinfunction "OUT_7") (pintype "output"))
    )
    (net (code "79") (name "Net-(U4C--IN)") (class "Default")
      (node (ref "C49") (pin "1") (pinfunction "1_1") (pintype "passive"))
      (node (ref "R80") (pin "2") (pinfunction "2_2") (pintype "passive"))
      (node (ref "R81") (pin "1") (pinfunction "1_1") (pintype "passive"))
      (node (ref "U4") (pin "9") (pinfunction "-IN_9") (pintype "input"))
    )
    (net (code "80") (name "Net-(U4C-OUT)") (class "Default")
      (node (ref "C49") (pin "2") (pinfunction "2_2") (pintype "passive"))
      (node (ref "R81") (pin "2") (pinfunction "2_2") (pintype "passive"))
      (node (ref "R98") (pin "1") (pinfunction "1_1") (pintype "passive"))
      (node (ref "U4") (pin "8") (pinfunction "OUT_8") (pintype "output"))
    )
    (net (code "81") (name "Net-(U4D--IN)") (class "Default")
      (node (ref "C48") (pin "1") (pinfunction "1_1") (pintype "passive"))
      (node (ref "R73") (pin "2") (pinfunction "2_2") (pintype "passive"))
      (node (ref "R74") (pin "1") (pinfunction "1_1") (pintype "passive"))
      (node (ref "U4") (pin "13") (pinfunction "-IN_13") (pintype "input"))
    )
    (net (code "82") (name "Net-(U4D-OUT)") (class "Default")
      (node (ref "C48") (pin "2") (pinfunction "2_2") (pintype "passive"))
      (node (ref "R74") (pin "2") (pinfunction "2_2") (pintype "passive"))
      (node (ref "R82") (pin "1") (pinfunction "1_1") (pintype "passive"))
      (node (ref "U4") (pin "14") (pinfunction "OUT_14") (pintype "output"))
    )
    (net (code "83") (name "Net-(U5A--IN)") (class "Default")
      (node (ref "R10") (pin "1") (pinfunction "1_1") (pintype "passive"))
      (node (ref "R11") (pin "2") (pinfunction "2_2") (pintype "passive"))
      (node (ref "U5") (pin "2") (pinfunction "-IN_2") (pintype "input"))
    )
    (net (code "84") (name "Net-(U5A-OUT)") (class "Default")
      (node (ref "R11") (pin "1") (pinfunction "1_1") (pintype "passive"))
      (node (ref "R16") (pin "2") (pinfunction "2_2") (pintype "passive"))
      (node (ref "U5") (pin "1") (pinfunction "OUT_1") (pintype "output"))
    )
    (net (code "85") (name "Net-(U5B--IN)") (class "Default")
      (node (ref "R8") (pin "1") (pinfunction "1_1") (pintype "passive"))
      (node (ref "R9") (pin "2") (pinfunction "2_2") (pintype "passive"))
      (node (ref "U5") (pin "6") (pinfunction "-IN_6") (pintype "input"))
    )
    (net (code "86") (name "Net-(U5B-OUT)") (class "Default")
      (node (ref "R14") (pin "2") (pinfunction "2_2") (pintype "passive"))
      (node (ref "R9") (pin "1") (pinfunction "1_1") (pintype "passive"))
      (node (ref "U5") (pin "7") (pinfunction "OUT_7") (pintype "output"))
    )
    (net (code "87") (name "Net-(U5C--IN)") (class "Default")
      (node (ref "R14") (pin "1") (pinfunction "1_1") (pintype "passive"))
      (node (ref "R15") (pin "2") (pinfunction "2_2") (pintype "passive"))
      (node (ref "U5") (pin "9") (pinfunction "-IN_9") (pintype "input"))
    )
    (net (code "88") (name "Net-(U5C-OUT)") (class "Default")
      (node (ref "R12") (pin "2") (pinfunction "2_2") (pintype "passive"))
      (node (ref "R15") (pin "1") (pinfunction "1_1") (pintype "passive"))
      (node (ref "U5") (pin "8") (pinfunction "OUT_8") (pintype "output"))
    )
    (net (code "89") (name "Net-(U5D--IN)") (class "Default")
      (node (ref "R16") (pin "1") (pinfunction "1_1") (pintype "passive"))
      (node (ref "R17") (pin "2") (pinfunction "2_2") (pintype "passive"))
      (node (ref "U5") (pin "13") (pinfunction "-IN_13") (pintype "input"))
    )
    (net (code "90") (name "Net-(U5D-OUT)") (class "Default")
      (node (ref "R13") (pin "2") (pinfunction "2_2") (pintype "passive"))
      (node (ref "R17") (pin "1") (pinfunction "1_1") (pintype "passive"))
      (node (ref "U5") (pin "14") (pinfunction "OUT_14") (pintype "output"))
    )
    (net (code "91") (name "Net-(U7A--IN)") (class "Default")
      (node (ref "C12") (pin "1") (pinfunction "1_1") (pintype "passive"))
      (node (ref "R110") (pin "2") (pinfunction "2_2") (pintype "passive"))
      (node (ref "R25") (pin "1") (pinfunction "1_1") (pintype "passive"))
      (node (ref "R26") (pin "2") (pinfunction "2_2") (pintype "passive"))
      (node (ref "R27") (pin "2") (pinfunction "2_2") (pintype "passive"))
      (node (ref "U7") (pin "2") (pinfunction "-IN_2") (pintype "input"))
    )
    (net (code "92") (name "Net-(U7B--IN)") (class "Default")
      (node (ref "C11") (pin "1") (pinfunction "1_1") (pintype "passive"))
      (node (ref "R109") (pin "2") (pinfunction "2_2") (pintype "passive"))
      (node (ref "R22") (pin "1") (pinfunction "1_1") (pintype "passive"))
      (node (ref "R23") (pin "2") (pinfunction "2_2") (pintype "passive"))
      (node (ref "R24") (pin "2") (pinfunction "2_2") (pintype "passive"))
      (node (ref "U7") (pin "6") (pinfunction "-IN_6") (pintype "input"))
    )
    (net (code "93") (name "Net-(U7C--IN)") (class "Default")
      (node (ref "C54") (pin "1") (pinfunction "1_1") (pintype "passive"))
      (node (ref "R105") (pin "1") (pinfunction "1_1") (pintype "passive"))
      (node (ref "R106") (pin "2") (pinfunction "2_2") (pintype "passive"))
      (node (ref "R107") (pin "2") (pinfunction "2_2") (pintype "passive"))
      (node (ref "R108") (pin "2") (pinfunction "2_2") (pintype "passive"))
      (node (ref "U7") (pin "9") (pinfunction "-IN_9") (pintype "input"))
    )
    (net (code "94") (name "Net-(U7D--IN)") (class "Default")
      (node (ref "C15") (pin "1") (pinfunction "1_1") (pintype "passive"))
      (node (ref "R111") (pin "2") (pinfunction "2_2") (pintype "passive"))
      (node (ref "R31") (pin "2") (pinfunction "2_2") (pintype "passive"))
      (node (ref "R32") (pin "2") (pinfunction "2_2") (pintype "passive"))
      (node (ref "R33") (pin "1") (pinfunction "1_1") (pintype "passive"))
      (node (ref "U7") (pin "13") (pinfunction "-IN_13") (pintype "input"))
    )
    (net (code "95") (name "Net-(U11A--IN)") (class "Default")
      (node (ref "C52") (pin "1") (pinfunction "1_1") (pintype "passive"))
      (node (ref "R102") (pin "2") (pinfunction "2_2") (pintype "passive"))
      (node (ref "R99") (pin "1") (pinfunction "1_1") (pintype "passive"))
      (node (ref "U11") (pin "2") (pinfunction "-IN_2") (pintype "input"))
    )
    (net (code "96") (name "Net-(U11A-OUT)") (class "Default")
      (node (ref "C52") (pin "2") (pinfunction "2_2") (pintype "passive"))
      (node (ref "R101") (pin "1") (pinfunction "1_1") (pintype "passive"))
      (node (ref "R99") (pin "2") (pinfunction "2_2") (pintype "passive"))
      (node (ref "U11") (pin "1") (pinfunction "OUT_1") (pintype "output"))
    )
    (net (code "97") (name "Net-(U11B--IN)") (class "Default")
      (node (ref "C53") (pin "1") (pinfunction "1_1") (pintype "passive"))
      (node (ref "R100") (pin "1") (pinfunction "1_1") (pintype "passive"))
      (node (ref "R104") (pin "2") (pinfunction "2_2") (pintype "passive"))
      (node (ref "U11") (pin "6") (pinfunction "-IN_6") (pintype "input"))
    )
    (net (code "98") (name "Net-(U11B-OUT)") (class "Default")
      (node (ref "C53") (pin "2") (pinfunction "2_2") (pintype "passive"))
      (node (ref "R100") (pin "2") (pinfunction "2_2") (pintype "passive"))
      (node (ref "R103") (pin "1") (pinfunction "1_1") (pintype "passive"))
      (node (ref "U11") (pin "7") (pinfunction "OUT_7") (pintype "output"))
    )
    (net (code "99") (name "Net-(U11C--IN)") (class "Default")
      (node (ref "C26") (pin "1") (pinfunction "1_1") (pintype "passive"))
      (node (ref "R103") (pin "2") (pinfunction "2_2") (pintype "passive"))
      (node (ref "R71") (pin "1") (pinfunction "1_1") (pintype "passive"))
      (node (ref "U11") (pin "9") (pinfunction "-IN_9") (pintype "input"))
    )
    (net (code "100") (name "Net-(U11C-OUT)") (class "Default")
      (node (ref "C26") (pin "2") (pinfunction "2_2") (pintype "passive"))
      (node (ref "R71") (pin "2") (pinfunction "2_2") (pintype "passive"))
      (node (ref "R72") (pin "1") (pinfunction "1_1") (pintype "passive"))
      (node (ref "U11") (pin "8") (pinfunction "OUT_8") (pintype "output"))
    )
    (net (code "101") (name "Net-(U11D--IN)") (class "Default")
      (node (ref "C27") (pin "1") (pinfunction "1_1") (pintype "passive"))
      (node (ref "R101") (pin "2") (pinfunction "2_2") (pintype "passive"))
      (node (ref "R66") (pin "1") (pinfunction "1_1") (pintype "passive"))
      (node (ref "U11") (pin "13") (pinfunction "-IN_13") (pintype "input"))
    )
    (net (code "102") (name "Net-(U11D-OUT)") (class "Default")
      (node (ref "C27") (pin "2") (pinfunction "2_2") (pintype "passive"))
      (node (ref "R66") (pin "2") (pinfunction "2_2") (pintype "passive"))
      (node (ref "R67") (pin "1") (pinfunction "1_1") (pintype "passive"))
      (node (ref "U11") (pin "14") (pinfunction "OUT_14") (pintype "output"))
    )
    (net (code "103") (name "Net-(U13A--IN)") (class "Default")
      (node (ref "U13") (pin "1") (pinfunction "OUT_1") (pintype "output"))
      (node (ref "U13") (pin "2") (pinfunction "-IN_2") (pintype "input"))
    )
    (net (code "104") (name "Net-(U13B--IN)") (class "Default")
      (node (ref "R112") (pin "1") (pinfunction "1_1") (pintype "passive"))
      (node (ref "R113") (pin "2") (pinfunction "2_2") (pintype "passive"))
      (node (ref "U13") (pin "6") (pinfunction "-IN_6") (pintype "input"))
    )
    (net (code "105") (name "Net-(U13B-OUT)") (class "Default")
      (node (ref "R113") (pin "1") (pinfunction "1_1") (pintype "passive"))
      (node (ref "R114") (pin "2") (pinfunction "2_2") (pintype "passive"))
      (node (ref "U13") (pin "7") (pinfunction "OUT_7") (pintype "output"))
    )
    (net (code "106") (name "Net-(U13C--IN)") (class "Default")
      (node (ref "R114") (pin "1") (pinfunction "1_1") (pintype "passive"))
      (node (ref "R115") (pin "2") (pinfunction "2_2") (pintype "passive"))
      (node (ref "U13") (pin "9") (pinfunction "-IN_9") (pintype "input"))
    )
    (net (code "107") (name "Net-(U13C-OUT)") (class "Default")
      (node (ref "R115") (pin "1") (pinfunction "1_1") (pintype "passive"))
      (node (ref "R38") (pin "2") (pinfunction "2_2") (pintype "passive"))
      (node (ref "U13") (pin "8") (pinfunction "OUT_8") (pintype "output"))
    )
    (net (code "108") (name "Net-(U13D--IN)") (class "Default")
      (node (ref "U13") (pin "13") (pinfunction "-IN_13") (pintype "input"))
      (node (ref "U13") (pin "14") (pinfunction "OUT_14") (pintype "output"))
    )
    (net (code "109") (name "Net-(U14A--IN)") (class "Default")
      (node (ref "C6") (pin "1") (pinfunction "1_1") (pintype "passive"))
      (node (ref "R20") (pin "2") (pinfunction "2_2") (pintype "passive"))
      (node (ref "R39") (pin "1") (pinfunction "1_1") (pintype "passive"))
      (node (ref "U14") (pin "2") (pinfunction "-IN_2") (pintype "input"))
    )
    (net (code "110") (name "Net-(U14A-OUT)") (class "Default")
      (node (ref "C6") (pin "2") (pinfunction "2_2") (pintype "passive"))
      (node (ref "R39") (pin "2") (pinfunction "2_2") (pintype "passive"))
      (node (ref "R42") (pin "1") (pinfunction "1_1") (pintype "passive"))
      (node (ref "U14") (pin "1") (pinfunction "OUT_1") (pintype "output"))
    )
    (net (code "111") (name "Net-(U14B--IN)") (class "Default")
      (node (ref "C7") (pin "1") (pinfunction "1_1") (pintype "passive"))
      (node (ref "R40") (pin "2") (pinfunction "2_2") (pintype "passive"))
      (node (ref "R41") (pin "1") (pinfunction "1_1") (pintype "passive"))
      (node (ref "U14") (pin "6") (pinfunction "-IN_6") (pintype "input"))
    )
    (net (code "112") (name "Net-(U14B-OUT)") (class "Default")
      (node (ref "C7") (pin "2") (pinfunction "2_2") (pintype "passive"))
      (node (ref "R41") (pin "2") (pinfunction "2_2") (pintype "passive"))
      (node (ref "R44") (pin "1") (pinfunction "1_1") (pintype "passive"))
      (node (ref "U14") (pin "7") (pinfunction "OUT_7") (pintype "output"))
    )
    (net (code "113") (name "Net-(U14C--IN)") (class "Default")
      (node (ref "C18") (pin "1") (pinfunction "1_1") (pintype "passive"))
      (node (ref "R44") (pin "2") (pinfunction "2_2") (pintype "passive"))
      (node (ref "R45") (pin "1") (pinfunction "1_1") (pintype "passive"))
      (node (ref "U14") (pin "9") (pinfunction "-IN_9") (pintype "input"))
    )
    (net (code "114") (name "Net-(U14C-OUT)") (class "Default")
      (node (ref "C18") (pin "2") (pinfunction "2_2") (pintype "passive"))
      (node (ref "R45") (pin "2") (pinfunction "2_2") (pintype "passive"))
      (node (ref "R47") (pin "1") (pinfunction "1_1") (pintype "passive"))
      (node (ref "U14") (pin "8") (pinfunction "OUT_8") (pintype "output"))
    )
    (net (code "115") (name "Net-(U14D--IN)") (class "Default")
      (node (ref "C17") (pin "1") (pinfunction "1_1") (pintype "passive"))
      (node (ref "R42") (pin "2") (pinfunction "2_2") (pintype "passive"))
      (node (ref "R43") (pin "1") (pinfunction "1_1") (pintype "passive"))
      (node (ref "U14") (pin "13") (pinfunction "-IN_13") (pintype "input"))
    )
    (net (code "116") (name "Net-(U14D-OUT)") (class "Default")
      (node (ref "C17") (pin "2") (pinfunction "2_2") (pintype "passive"))
      (node (ref "R43") (pin "2") (pinfunction "2_2") (pintype "passive"))
      (node (ref "R46") (pin "1") (pinfunction "1_1") (pintype "passive"))
      (node (ref "U14") (pin "14") (pinfunction "OUT_14") (pintype "output"))
    )
    (net (code "117") (name "Net-(U15-A)") (class "Default")
      (node (ref "D5") (pin "C") (pinfunction "C_C") (pintype "passive"))
      (node (ref "R63") (pin "1") (pinfunction "1_1") (pintype "passive"))
      (node (ref "U15") (pin "1") (pinfunction "A_1") (pintype "bidirectional"))
    )
    (net (code "118") (name "Net-(U16A--IN)") (class "Default")
      (node (ref "C25") (pin "1") (pinfunction "1_1") (pintype "passive"))
      (node (ref "R52") (pin "1") (pinfunction "1_1") (pintype "passive"))
      (node (ref "R57") (pin "2") (pinfunction "2_2") (pintype "passive"))
      (node (ref "U16") (pin "2") (pinfunction "-IN_2") (pintype "input"))
    )
    (net (code "119") (name "Net-(U16A-OUT)") (class "Default")
      (node (ref "C25") (pin "2") (pinfunction "2_2") (pintype "passive"))
      (node (ref "R52") (pin "2") (pinfunction "2_2") (pintype "passive"))
      (node (ref "R54") (pin "1") (pinfunction "1_1") (pintype "passive"))
      (node (ref "U16") (pin "1") (pinfunction "OUT_1") (pintype "output"))
    )
    (net (code "120") (name "Net-(U16B--IN)") (class "Default")
      (node (ref "C28") (pin "1") (pinfunction "1_1") (pintype "passive"))
      (node (ref "R53") (pin "1") (pinfunction "1_1") (pintype "passive"))
      (node (ref "R59") (pin "2") (pinfunction "2_2") (pintype "passive"))
      (node (ref "U16") (pin "6") (pinfunction "-IN_6") (pintype "input"))
    )
    (net (code "121") (name "Net-(U16B-OUT)") (class "Default")
      (node (ref "C28") (pin "2") (pinfunction "2_2") (pintype "passive"))
      (node (ref "R53") (pin "2") (pinfunction "2_2") (pintype "passive"))
      (node (ref "R58") (pin "1") (pinfunction "1_1") (pintype "passive"))
      (node (ref "U16") (pin "7") (pinfunction "OUT_7") (pintype "output"))
    )
    (net (code "122") (name "Net-(U16C--IN)") (class "Default")
      (node (ref "C19") (pin "1") (pinfunction "1_1") (pintype "passive"))
      (node (ref "R50") (pin "1") (pinfunction "1_1") (pintype "passive"))
      (node (ref "R58") (pin "2") (pinfunction "2_2") (pintype "passive"))
      (node (ref "U16") (pin "9") (pinfunction "-IN_9") (pintype "input"))
    )
    (net (code "123") (name "Net-(U16C-OUT)") (class "Default")
      (node (ref "C19") (pin "2") (pinfunction "2_2") (pintype "passive"))
      (node (ref "R50") (pin "2") (pinfunction "2_2") (pintype "passive"))
      (node (ref "R51") (pin "1") (pinfunction "1_1") (pintype "passive"))
      (node (ref "U16") (pin "8") (pinfunction "OUT_8") (pintype "output"))
    )
    (net (code "124") (name "Net-(U16D--IN)") (class "Default")
      (node (ref "C24") (pin "1") (pinfunction "1_1") (pintype "passive"))
      (node (ref "R48") (pin "1") (pinfunction "1_1") (pintype "passive"))
      (node (ref "R54") (pin "2") (pinfunction "2_2") (pintype "passive"))
      (node (ref "U16") (pin "13") (pinfunction "-IN_13") (pintype "input"))
    )
    (net (code "125") (name "Net-(U16D-OUT)") (class "Default")
      (node (ref "C24") (pin "2") (pinfunction "2_2") (pintype "passive"))
      (node (ref "R48") (pin "2") (pinfunction "2_2") (pintype "passive"))
      (node (ref "R49") (pin "1") (pinfunction "1_1") (pintype "passive"))
      (node (ref "U16") (pin "14") (pinfunction "OUT_14") (pintype "output"))
    )
    (net (code "126") (name "OLED_CMD") (class "Default")
      (node (ref "U_DAISY") (pin "10") (pinfunction "GPIO9(SPI1_MISO)_10") (pintype "bidirectional"))
      (node (ref "U_DAISY") (pin "B10") (pinfunction "GPIO9(SPI1_MISO)_B10") (pintype "bidirectional"))
      (node (ref "U_OLED") (pin "6") (pinfunction "DC_6") (pintype "bidirectional"))
    )
    (net (code "127") (name "OLED_CS") (class "Default")
      (node (ref "U_DAISY") (pin "8") (pinfunction "GPIO7(SPI1_NSS)_8") (pintype "bidirectional"))
      (node (ref "U_DAISY") (pin "B8") (pinfunction "GPIO7(SPI1_NSS)_B8") (pintype "bidirectional"))
      (node (ref "U_OLED") (pin "7") (pinfunction "CS_7") (pintype "bidirectional"))
    )
    (net (code "128") (name "OLED_DATA") (class "Default")
      (node (ref "U_DAISY") (pin "11") (pinfunction "GPIO10(SPI1_MOSI)_11") (pintype "bidirectional"))
      (node (ref "U_DAISY") (pin "B11") (pinfunction "GPIO10(SPI1_MOSI)_B11") (pintype "bidirectional"))
      (node (ref "U_OLED") (pin "4") (pinfunction "SDA_4") (pintype "bidirectional"))
    )
    (net (code "129") (name "OLED_RST") (class "Default")
      (node (ref "U_DAISY") (pin "37") (pinfunction "GPIO30(USB_HS_D+)_37") (pintype "bidirectional"))
      (node (ref "U_DAISY") (pin "B37") (pinfunction "GPIO30(USB_HS_D+)_B37") (pintype "bidirectional"))
      (node (ref "U_OLED") (pin "5") (pinfunction "RES_5") (pintype "bidirectional"))
    )
    (net (code "130") (name "OLED_SCK") (class "Default")
      (node (ref "U_DAISY") (pin "9") (pinfunction "GPIO8(SPI1_SCK)_9") (pintype "bidirectional"))
      (node (ref "U_DAISY") (pin "B9") (pinfunction "GPIO8(SPI1_SCK)_B9") (pintype "bidirectional"))
      (node (ref "U_OLED") (pin "3") (pinfunction "SCL_3") (pintype "bidirectional"))
    )
    (net (code "131") (name "SAI2_FS_A") (class "Default")
      (node (ref "U2") (pin "14") (pinfunction "LRCK_14") (pintype "bidirectional"))
      (node (ref "U_DAISY") (pin "34") (pinfunction "GPIO27(SAI2_FS_B)_34") (pintype "bidirectional"))
      (node (ref "U_DAISY") (pin "B34") (pinfunction "GPIO27(SAI2_FS_B)_B34") (pintype "bidirectional"))
    )
    (net (code "132") (name "SAI2_MCLK") (class "Default")
      (node (ref "U2") (pin "15") (pinfunction "MCLK_15") (pintype "bidirectional"))
      (node (ref "U_DAISY") (pin "31") (pinfunction "GPIO24(ADC9)_31") (pintype "bidirectional"))
      (node (ref "U_DAISY") (pin "B31") (pinfunction "GPIO24(ADC9)_B31") (pintype "bidirectional"))
    )
    (net (code "133") (name "SAI2_SCK_A") (class "Default")
      (node (ref "U2") (pin "16") (pinfunction "BCLK_16") (pintype "bidirectional"))
      (node (ref "U_DAISY") (pin "35") (pinfunction "GPIO28(ADC11)_35") (pintype "bidirectional"))
      (node (ref "U_DAISY") (pin "B35") (pinfunction "GPIO28(ADC11)_B35") (pintype "bidirectional"))
    )
    (net (code "134") (name "SAI2_SD_A") (class "Default")
      (node (ref "U2") (pin "13") (pinfunction "SDI_13") (pintype "bidirectional"))
      (node (ref "U_DAISY") (pin "33") (pinfunction "GPIO26(SAI2_SD_A)_33") (pintype "bidirectional"))
      (node (ref "U_DAISY") (pin "B33") (pinfunction "GPIO26(SAI2_SD_A)_B33") (pintype "bidirectional"))
    )
    (net (code "135") (name "SAI2_SD_B") (class "Default")
      (node (ref "U2") (pin "8") (pinfunction "SDO_8") (pintype "bidirectional"))
      (node (ref "U_DAISY") (pin "32") (pinfunction "GPIO25(ADC10)_32") (pintype "bidirectional"))
      (node (ref "U_DAISY") (pin "B32") (pinfunction "GPIO25(ADC10)_B32") (pintype "bidirectional"))
    )
    (net (code "136") (name "SD_CK") (class "Default")
      (node (ref "U3") (pin "P$5") (pinfunction "SCK_P$5") (pintype "bidirectional"))
      (node (ref "U_DAISY") (pin "7") (pinfunction "GPIO6(SDMMC1_CK)_7") (pintype "bidirectional"))
      (node (ref "U_DAISY") (pin "B7") (pinfunction "GPIO6(SDMMC1_CK)_B7") (pintype "bidirectional"))
    )
    (net (code "137") (name "SD_CMD") (class "Default")
      (node (ref "R5") (pin "1") (pinfunction "1_1") (pintype "passive"))
      (node (ref "U3") (pin "P$3") (pinfunction "CMD/DI_P$3") (pintype "bidirectional"))
      (node (ref "U_DAISY") (pin "6") (pinfunction "GPIO5(SDMMC1_CMD)_6") (pintype "bidirectional"))
      (node (ref "U_DAISY") (pin "B6") (pinfunction "GPIO5(SDMMC1_CMD)_B6") (pintype "bidirectional"))
    )
    (net (code "138") (name "SD_D0") (class "Default")
      (node (ref "R6") (pin "1") (pinfunction "1_1") (pintype "passive"))
      (node (ref "U3") (pin "P$7") (pinfunction "D0/DO_P$7") (pintype "bidirectional"))
      (node (ref "U_DAISY") (pin "5") (pinfunction "GPIO4(SDMMC1_D0)_5") (pintype "bidirectional"))
      (node (ref "U_DAISY") (pin "B5") (pinfunction "GPIO4(SDMMC1_D0)_B5") (pintype "bidirectional"))
    )
    (net (code "139") (name "SD_D1") (class "Default")
      (node (ref "R7") (pin "1") (pinfunction "1_1") (pintype "passive"))
      (node (ref "U3") (pin "P$8") (pinfunction "D1/RSV_P$8") (pintype "bidirectional"))
      (node (ref "U_DAISY") (pin "4") (pinfunction "GPIO3(SDMMC1_D1)_4") (pintype "bidirectional"))
      (node (ref "U_DAISY") (pin "B4") (pinfunction "GPIO3(SDMMC1_D1)_B4") (pintype "bidirectional"))
    )
    (net (code "140") (name "SD_D2") (class "Default")
      (node (ref "R3") (pin "1") (pinfunction "1_1") (pintype "passive"))
      (node (ref "U3") (pin "P$1") (pinfunction "D2/NC_P$1") (pintype "bidirectional"))
      (node (ref "U_DAISY") (pin "3") (pinfunction "GPIO2(SDMMC1_D2)_3") (pintype "bidirectional"))
      (node (ref "U_DAISY") (pin "B3") (pinfunction "GPIO2(SDMMC1_D2)_B3") (pintype "bidirectional"))
    )
    (net (code "141") (name "SD_D3") (class "Default")
      (node (ref "R4") (pin "1") (pinfunction "1_1") (pintype "passive"))
      (node (ref "U3") (pin "P$2") (pinfunction "D3/CS_P$2") (pintype "bidirectional"))
      (node (ref "U_DAISY") (pin "2") (pinfunction "GPIO1(SDMMC1_D3)_2") (pintype "bidirectional"))
      (node (ref "U_DAISY") (pin "B2") (pinfunction "GPIO1(SDMMC1_D3)_B2") (pintype "bidirectional"))
    )
    (net (code "142") (name "SPI1_MOSI_IN") (class "Default")
      (node (ref "J_GATE_IN_1") (pin "TIP") (pinfunction "TIP_TIP") (pintype "passive"))
      (node (ref "R21") (pin "1") (pinfunction "1_1") (pintype "passive"))
    )
    (net (code "143") (name "SPI1_NSS_OUT") (class "Default")
      (node (ref "J_GATE_OUT") (pin "TIP") (pinfunction "TIP_TIP") (pintype "passive"))
      (node (ref "R38") (pin "1") (pinfunction "1_1") (pintype "passive"))
    )
    (net (code "144") (name "USART1_RX") (class "Default")
      (node (ref "R64") (pin "2") (pinfunction "2_2") (pintype "passive"))
      (node (ref "U15") (pin "4") (pinfunction "OUT_4") (pintype "bidirectional"))
      (node (ref "U_DAISY") (pin "15") (pinfunction "GPIO14(USART1_RX)_15") (pintype "bidirectional"))
      (node (ref "U_DAISY") (pin "B15") (pinfunction "GPIO14(USART1_RX)_B15") (pintype "bidirectional"))
    )
    (net (code "145") (name "USART1_TX") (class "Default")
      (node (ref "R2") (pin "2") (pinfunction "2_2") (pintype "passive"))
      (node (ref "U_DAISY") (pin "14") (pinfunction "GPIO13(USART1_TX)_14") (pintype "bidirectional"))
      (node (ref "U_DAISY") (pin "B14") (pinfunction "GPIO13(USART1_TX)_B14") (pintype "bidirectional"))
    )
    (net (code "146") (name "unconnected-(J_AUDIO_IN_1-PadNORM)") (class "Default")
      (node (ref "J_AUDIO_IN_1") (pin "NORM") (pinfunction "NORM_NORM") (pintype "passive"))
    )
    (net (code "147") (name "unconnected-(J_AUDIO_OUT_1-PadNORM)") (class "Default")
      (node (ref "J_AUDIO_OUT_1") (pin "NORM") (pinfunction "NORM_NORM") (pintype "passive"))
    )
    (net (code "148") (name "unconnected-(J_AUDIO_OUT_2-PadNORM)") (class "Default")
      (node (ref "J_AUDIO_OUT_2") (pin "NORM") (pinfunction "NORM_NORM") (pintype "passive"))
    )
    (net (code "149") (name "unconnected-(J_AUDIO_OUT_3-PadNORM)") (class "Default")
      (node (ref "J_AUDIO_OUT_3") (pin "NORM") (pinfunction "NORM_NORM") (pintype "passive"))
    )
    (net (code "150") (name "unconnected-(J_AUDIO_OUT_4-PadNORM)") (class "Default")
      (node (ref "J_AUDIO_OUT_4") (pin "NORM") (pinfunction "NORM_NORM") (pintype "passive"))
    )
    (net (code "151") (name "unconnected-(J_CV_1-PadNORM)") (class "Default")
      (node (ref "J_CV_1") (pin "NORM") (pinfunction "NORM_NORM") (pintype "passive"))
    )
    (net (code "152") (name "unconnected-(J_CV_2-PadNORM)") (class "Default")
      (node (ref "J_CV_2") (pin "NORM") (pinfunction "NORM_NORM") (pintype "passive"))
    )
    (net (code "153") (name "unconnected-(J_CV_3-PadNORM)") (class "Default")
      (node (ref "J_CV_3") (pin "NORM") (pinfunction "NORM_NORM") (pintype "passive"))
    )
    (net (code "154") (name "unconnected-(J_CV_4-PadNORM)") (class "Default")
      (node (ref "J_CV_4") (pin "NORM") (pinfunction "NORM_NORM") (pintype "passive"))
    )
    (net (code "155") (name "unconnected-(J_CV_OUT_1-PadNORM)") (class "Default")
      (node (ref "J_CV_OUT_1") (pin "NORM") (pinfunction "NORM_NORM") (pintype "passive"))
    )
    (net (code "156") (name "unconnected-(J_CV_OUT_2-PadNORM)") (class "Default")
      (node (ref "J_CV_OUT_2") (pin "NORM") (pinfunction "NORM_NORM") (pintype "passive"))
    )
    (net (code "157") (name "unconnected-(J_GATE_IN_1-PadNORM)") (class "Default")
      (node (ref "J_GATE_IN_1") (pin "NORM") (pinfunction "NORM_NORM") (pintype "passive"))
    )
    (net (code "158") (name "unconnected-(J_GATE_IN_2-PadNORM)") (class "Default")
      (node (ref "J_GATE_IN_2") (pin "NORM") (pinfunction "NORM_NORM") (pintype "passive"))
    )
    (net (code "159") (name "unconnected-(J_GATE_OUT-PadNORM)") (class "Default")
      (node (ref "J_GATE_OUT") (pin "NORM") (pinfunction "NORM_NORM") (pintype "passive"))
    )
  )
)
